# tester-rp.net
KiCad netlist of a schematic drawn in EAGLE
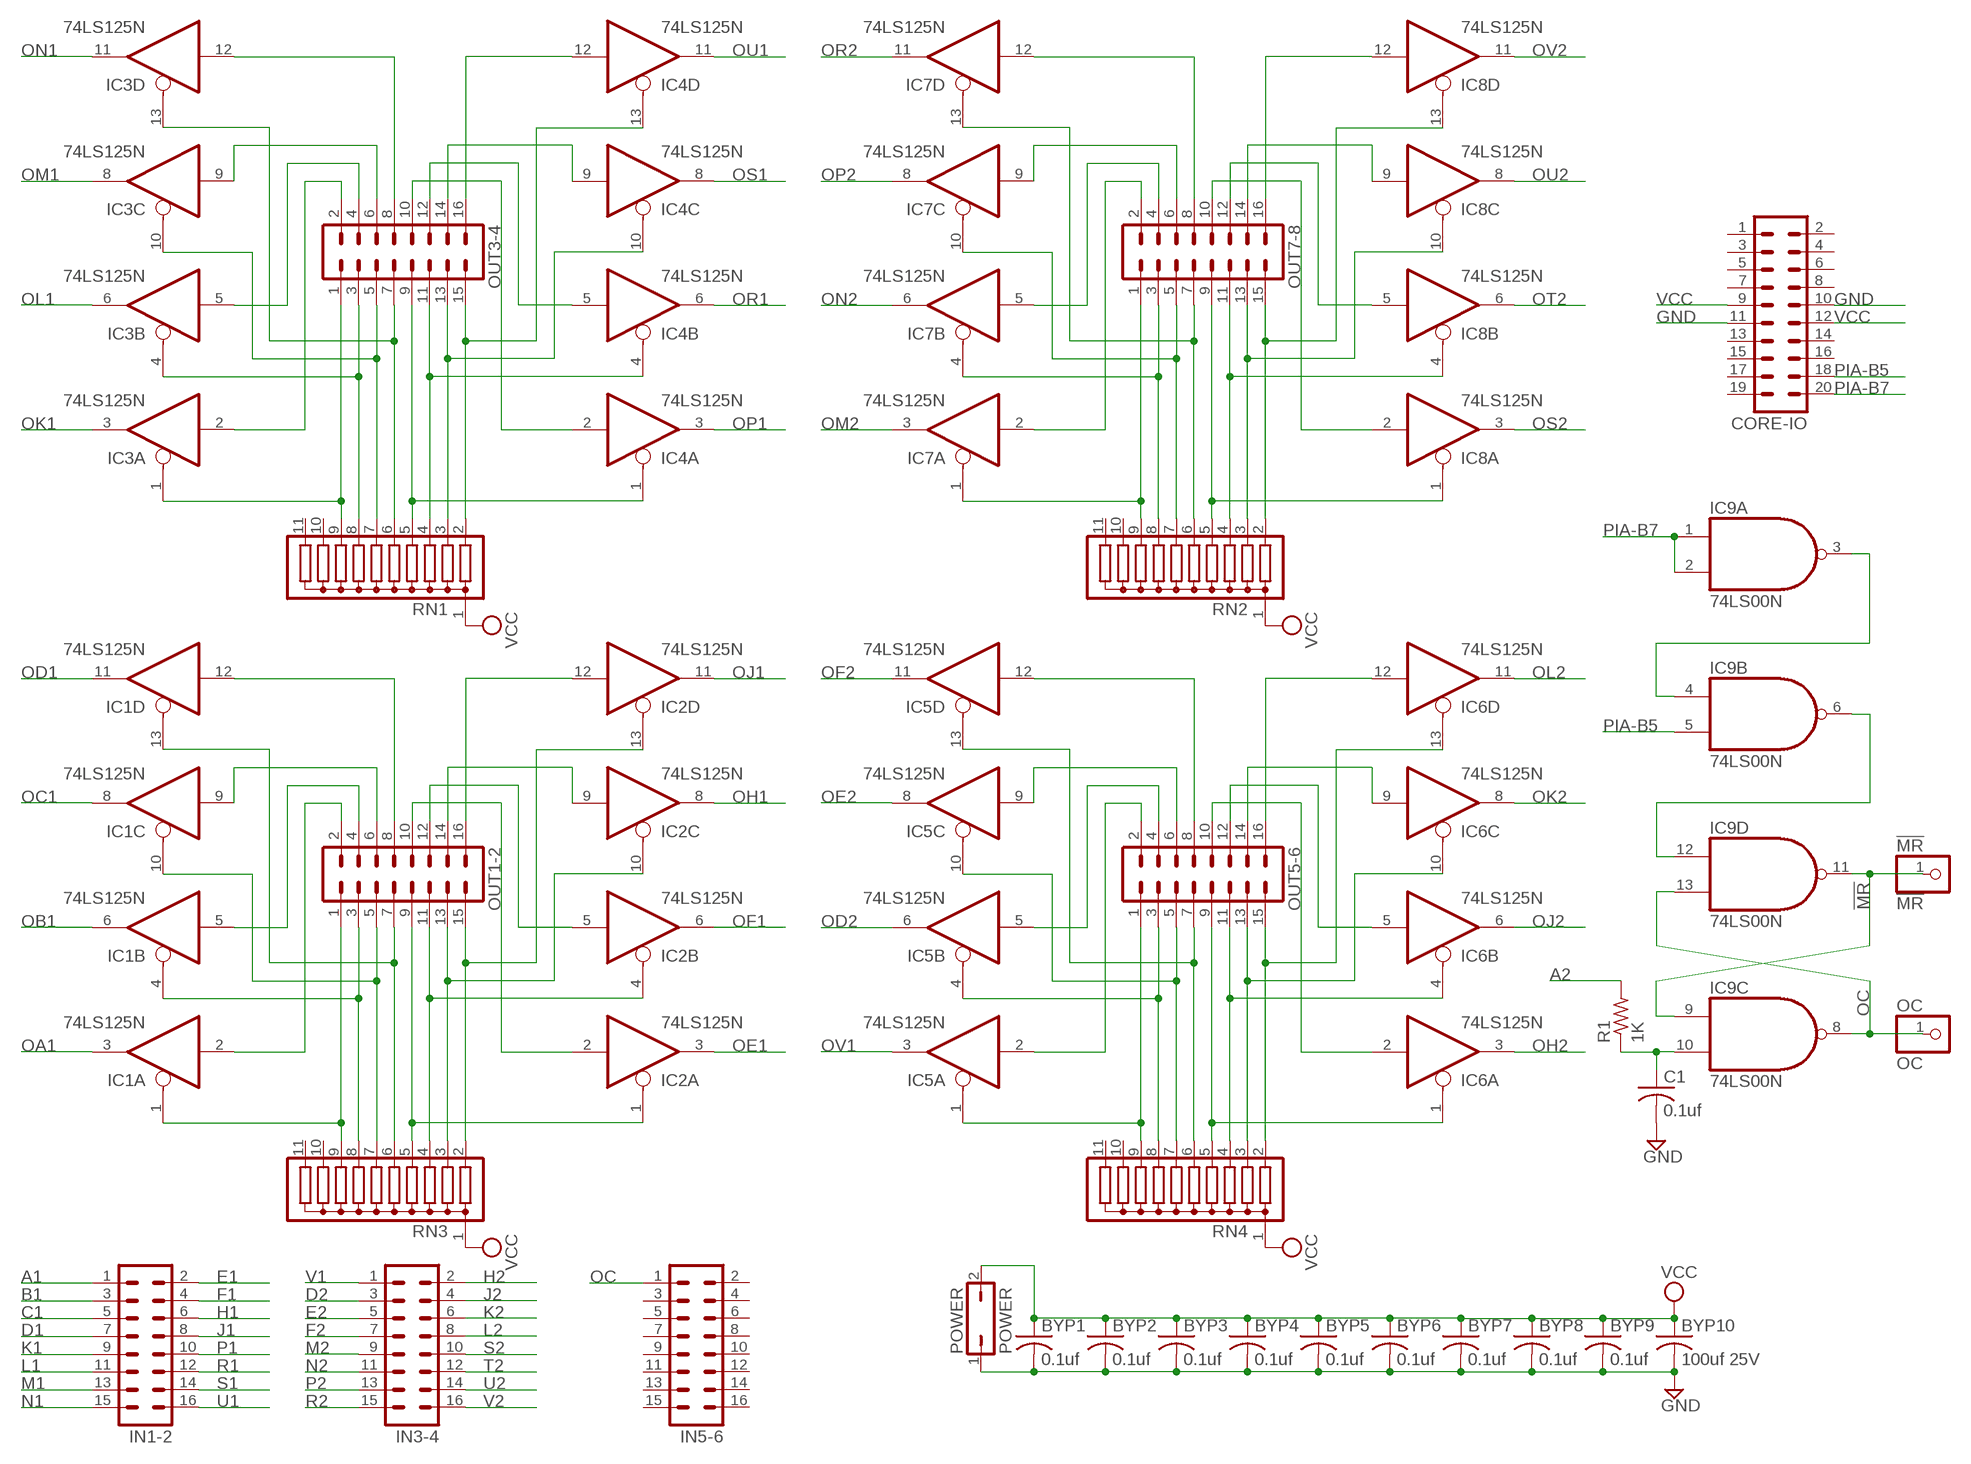
[diagram p0: schematic, sheet 1]
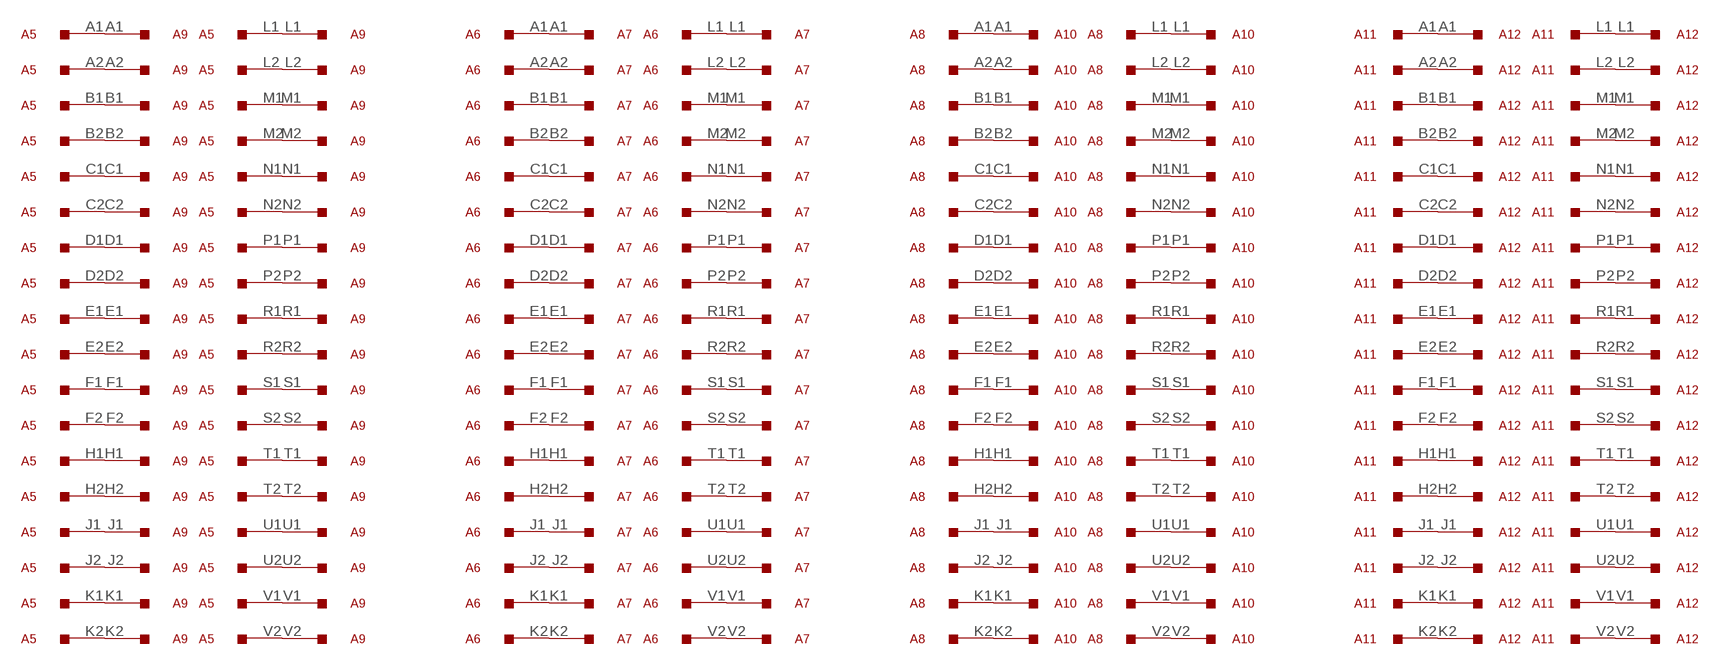
[diagram p1: schematic, sheet 2]
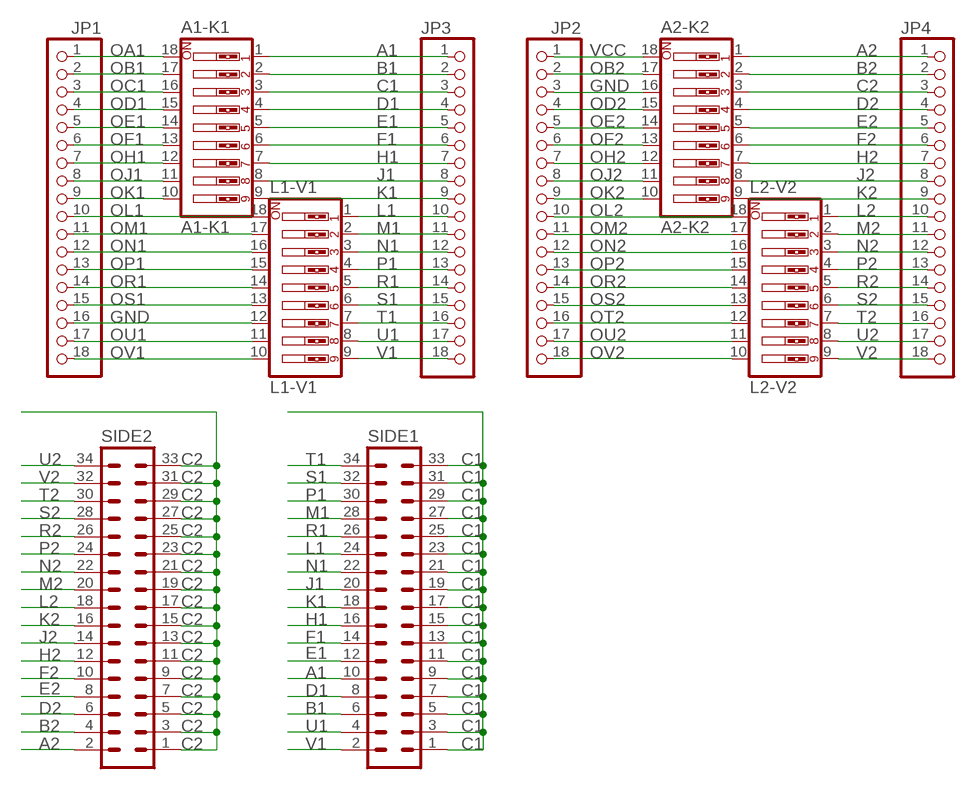
[diagram p2: schematic, sheet 3]

(export (version "E")
  (design (tool "Eeschema 10.0.6"))
  (components
    (comp (ref "!MR")
      (value "!MR")
      (footprint "eagle-import:1X01")
      (libsource (lib "eagle-import") (part "PINHD-1X1"))
    )
    (comp (ref "BYP1")
      (value "0.1uf")
      (footprint "eagle-import:C050-025X075")
      (libsource (lib "eagle-import") (part "C-US050-025X075"))
    )
    (comp (ref "BYP2")
      (value "0.1uf")
      (footprint "eagle-import:C050-025X075")
      (libsource (lib "eagle-import") (part "C-US050-025X075"))
    )
    (comp (ref "BYP3")
      (value "0.1uf")
      (footprint "eagle-import:C050-025X075")
      (libsource (lib "eagle-import") (part "C-US050-025X075"))
    )
    (comp (ref "BYP4")
      (value "0.1uf")
      (footprint "eagle-import:C050-025X075")
      (libsource (lib "eagle-import") (part "C-US050-025X075"))
    )
    (comp (ref "BYP5")
      (value "0.1uf")
      (footprint "eagle-import:C050-025X075")
      (libsource (lib "eagle-import") (part "C-US050-025X075"))
    )
    (comp (ref "BYP6")
      (value "0.1uf")
      (footprint "eagle-import:C050-025X075")
      (libsource (lib "eagle-import") (part "C-US050-025X075"))
    )
    (comp (ref "BYP7")
      (value "0.1uf")
      (footprint "eagle-import:C050-025X075")
      (libsource (lib "eagle-import") (part "C-US050-025X075"))
    )
    (comp (ref "BYP8")
      (value "0.1uf")
      (footprint "eagle-import:C050-025X075")
      (libsource (lib "eagle-import") (part "C-US050-025X075"))
    )
    (comp (ref "BYP9")
      (value "0.1uf")
      (footprint "eagle-import:C050-025X075")
      (libsource (lib "eagle-import") (part "C-US050-025X075"))
    )
    (comp (ref "BYP10")
      (value "100uf 25V")
      (footprint "eagle-import:C150-064X183")
      (libsource (lib "eagle-import") (part "C-US150-064X183"))
    )
    (comp (ref "C1")
      (value "0.1uf")
      (footprint "eagle-import:C050-025X075")
      (libsource (lib "eagle-import") (part "C-US050-025X075"))
    )
    (comp (ref "CORE-IO")
      (value "MA10-2")
      (footprint "eagle-import:MA10-2")
      (libsource (lib "eagle-import") (part "MA10-2"))
    )
    (comp (ref "IC1")
      (value "74LS125N")
      (footprint "eagle-import:DIL14")
      (libsource (lib "eagle-import") (part "74125NLS"))
    )
    (comp (ref "IC2")
      (value "74LS125N")
      (footprint "eagle-import:DIL14")
      (libsource (lib "eagle-import") (part "74125NLS"))
    )
    (comp (ref "IC3")
      (value "74LS125N")
      (footprint "eagle-import:DIL14")
      (libsource (lib "eagle-import") (part "74125NLS"))
    )
    (comp (ref "IC4")
      (value "74LS125N")
      (footprint "eagle-import:DIL14")
      (libsource (lib "eagle-import") (part "74125NLS"))
    )
    (comp (ref "IC5")
      (value "74LS125N")
      (footprint "eagle-import:DIL14")
      (libsource (lib "eagle-import") (part "74125NLS"))
    )
    (comp (ref "IC6")
      (value "74LS125N")
      (footprint "eagle-import:DIL14")
      (libsource (lib "eagle-import") (part "74125NLS"))
    )
    (comp (ref "IC7")
      (value "74LS125N")
      (footprint "eagle-import:DIL14")
      (libsource (lib "eagle-import") (part "74125NLS"))
    )
    (comp (ref "IC8")
      (value "74LS125N")
      (footprint "eagle-import:DIL14")
      (libsource (lib "eagle-import") (part "74125NLS"))
    )
    (comp (ref "IC9")
      (value "74LS00N")
      (footprint "eagle-import:DIL14")
      (libsource (lib "eagle-import") (part "7400NLS"))
    )
    (comp (ref "IN1-2")
      (value "MA08-2")
      (footprint "eagle-import:MA08-2")
      (libsource (lib "eagle-import") (part "MA08-2"))
    )
    (comp (ref "IN3-4")
      (value "MA08-2")
      (footprint "eagle-import:MA08-2")
      (libsource (lib "eagle-import") (part "MA08-2"))
    )
    (comp (ref "IN5-6")
      (value "MA08-2")
      (footprint "eagle-import:MA08-2")
      (libsource (lib "eagle-import") (part "MA08-2"))
    )
    (comp (ref "OC")
      (value "OC")
      (footprint "eagle-import:1X01")
      (libsource (lib "eagle-import") (part "PINHD-1X1"))
    )
    (comp (ref "OUT1-2")
      (value "MA08-2")
      (footprint "eagle-import:MA08-2")
      (libsource (lib "eagle-import") (part "MA08-2"))
    )
    (comp (ref "OUT3-4")
      (value "MA08-2")
      (footprint "eagle-import:MA08-2")
      (libsource (lib "eagle-import") (part "MA08-2"))
    )
    (comp (ref "OUT5-6")
      (value "MA08-2")
      (footprint "eagle-import:MA08-2")
      (libsource (lib "eagle-import") (part "MA08-2"))
    )
    (comp (ref "OUT7-8")
      (value "MA08-2")
      (footprint "eagle-import:MA08-2")
      (libsource (lib "eagle-import") (part "MA08-2"))
    )
    (comp (ref "POWER")
      (value "POWER")
      (footprint "eagle-import:JP1")
      (libsource (lib "eagle-import") (part "JP1Q"))
    )
    (comp (ref "R1")
      (value "1K")
      (footprint "eagle-import:0207_10")
      (libsource (lib "eagle-import") (part "R-US_0207/10"))
    )
    (comp (ref "RN1")
      (value "G10R")
      (footprint "eagle-import:SIL11")
      (libsource (lib "eagle-import") (part "G10R"))
    )
    (comp (ref "RN2")
      (value "G10R")
      (footprint "eagle-import:SIL11")
      (libsource (lib "eagle-import") (part "G10R"))
    )
    (comp (ref "RN3")
      (value "G10R")
      (footprint "eagle-import:SIL11")
      (libsource (lib "eagle-import") (part "G10R"))
    )
    (comp (ref "RN4")
      (value "G10R")
      (footprint "eagle-import:SIL11")
      (libsource (lib "eagle-import") (part "G10R"))
    )
    (comp (ref "A1-K1")
      (value "A1-K1")
      (footprint "eagle-import:EDG-09")
      (libsource (lib "eagle-import") (part "SW_DIP-9"))
    )
    (comp (ref "A2-K2")
      (value "A2-K2")
      (footprint "eagle-import:EDG-09")
      (libsource (lib "eagle-import") (part "SW_DIP-9"))
    )
    (comp (ref "JP1")
      (value "PINHD-1X18")
      (footprint "eagle-import:1X18")
      (libsource (lib "eagle-import") (part "PINHD-1X18"))
    )
    (comp (ref "JP2")
      (value "PINHD-1X18")
      (footprint "eagle-import:1X18")
      (libsource (lib "eagle-import") (part "PINHD-1X18"))
    )
    (comp (ref "JP3")
      (value "PINHD-1X18")
      (footprint "eagle-import:1X18")
      (libsource (lib "eagle-import") (part "PINHD-1X18"))
    )
    (comp (ref "JP4")
      (value "PINHD-1X18")
      (footprint "eagle-import:1X18")
      (libsource (lib "eagle-import") (part "PINHD-1X18"))
    )
    (comp (ref "L1-V1")
      (value "L1-V1")
      (footprint "eagle-import:EDG-09")
      (libsource (lib "eagle-import") (part "SW_DIP-9"))
    )
    (comp (ref "L2-V2")
      (value "L2-V2")
      (footprint "eagle-import:EDG-09")
      (libsource (lib "eagle-import") (part "SW_DIP-9"))
    )
    (comp (ref "SIDE1")
      (value "MA17-2")
      (footprint "eagle-import:MA17-2")
      (libsource (lib "eagle-import") (part "MA17-2"))
    )
    (comp (ref "SIDE2")
      (value "MA17-2")
      (footprint "eagle-import:MA17-2")
      (libsource (lib "eagle-import") (part "MA17-2"))
    )
    (comp (ref "A5")
      (value "M916")
      (footprint "eagle-import:H807")
      (libsource (lib "eagle-import") (part "M916"))
    )
    (comp (ref "A6")
      (value "M916")
      (footprint "eagle-import:H807")
      (libsource (lib "eagle-import") (part "M916"))
    )
    (comp (ref "A7")
      (value "M916")
      (footprint "eagle-import:H807")
      (libsource (lib "eagle-import") (part "M916"))
    )
    (comp (ref "A8")
      (value "M916")
      (footprint "eagle-import:H807")
      (libsource (lib "eagle-import") (part "M916"))
    )
    (comp (ref "A9")
      (value "M916")
      (footprint "eagle-import:H807")
      (libsource (lib "eagle-import") (part "M916"))
    )
    (comp (ref "A10")
      (value "M916")
      (footprint "eagle-import:H807")
      (libsource (lib "eagle-import") (part "M916"))
    )
    (comp (ref "A11")
      (value "M916")
      (footprint "eagle-import:H807")
      (libsource (lib "eagle-import") (part "M916"))
    )
    (comp (ref "A12")
      (value "M916")
      (footprint "eagle-import:H807")
      (libsource (lib "eagle-import") (part "M916"))
    )
  )
  (nets
    (net (code "1") (name "A1") (class "Default")
      (node (ref "A1-K1") (pin "1") (pinfunction "1_1") (pintype "passive"))
      (node (ref "IN1-2") (pin "1") (pinfunction "1_1") (pintype "passive"))
      (node (ref "JP3") (pin "1") (pinfunction "1_1") (pintype "passive"))
      (node (ref "SIDE1") (pin "10") (pinfunction "10_10") (pintype "passive"))
    )
    (net (code "2") (name "A2") (class "Default")
      (node (ref "A2-K2") (pin "1") (pinfunction "1_1") (pintype "passive"))
      (node (ref "JP4") (pin "1") (pinfunction "1_1") (pintype "passive"))
      (node (ref "R1") (pin "2") (pinfunction "2_2") (pintype "passive"))
      (node (ref "SIDE2") (pin "2") (pinfunction "2_2") (pintype "passive"))
    )
    (net (code "3") (name "B1") (class "Default")
      (node (ref "A1-K1") (pin "2") (pinfunction "2_2") (pintype "passive"))
      (node (ref "IN1-2") (pin "3") (pinfunction "3_3") (pintype "passive"))
      (node (ref "JP3") (pin "2") (pinfunction "2_2") (pintype "passive"))
      (node (ref "SIDE1") (pin "6") (pinfunction "6_6") (pintype "passive"))
    )
    (net (code "4") (name "B2") (class "Default")
      (node (ref "A2-K2") (pin "2") (pinfunction "2_2") (pintype "passive"))
      (node (ref "JP4") (pin "2") (pinfunction "2_2") (pintype "passive"))
      (node (ref "SIDE2") (pin "4") (pinfunction "4_4") (pintype "passive"))
    )
    (net (code "5") (name "C1") (class "Default")
      (node (ref "A1-K1") (pin "3") (pinfunction "3_3") (pintype "passive"))
      (node (ref "IN1-2") (pin "5") (pinfunction "5_5") (pintype "passive"))
      (node (ref "JP3") (pin "3") (pinfunction "3_3") (pintype "passive"))
      (node (ref "SIDE1") (pin "1") (pinfunction "1_1") (pintype "passive"))
      (node (ref "SIDE1") (pin "11") (pinfunction "11_11") (pintype "passive"))
      (node (ref "SIDE1") (pin "13") (pinfunction "13_13") (pintype "passive"))
      (node (ref "SIDE1") (pin "15") (pinfunction "15_15") (pintype "passive"))
      (node (ref "SIDE1") (pin "17") (pinfunction "17_17") (pintype "passive"))
      (node (ref "SIDE1") (pin "19") (pinfunction "19_19") (pintype "passive"))
      (node (ref "SIDE1") (pin "21") (pinfunction "21_21") (pintype "passive"))
      (node (ref "SIDE1") (pin "23") (pinfunction "23_23") (pintype "passive"))
      (node (ref "SIDE1") (pin "25") (pinfunction "25_25") (pintype "passive"))
      (node (ref "SIDE1") (pin "27") (pinfunction "27_27") (pintype "passive"))
      (node (ref "SIDE1") (pin "29") (pinfunction "29_29") (pintype "passive"))
      (node (ref "SIDE1") (pin "3") (pinfunction "3_3") (pintype "passive"))
      (node (ref "SIDE1") (pin "31") (pinfunction "31_31") (pintype "passive"))
      (node (ref "SIDE1") (pin "33") (pinfunction "33_33") (pintype "passive"))
      (node (ref "SIDE1") (pin "5") (pinfunction "5_5") (pintype "passive"))
      (node (ref "SIDE1") (pin "7") (pinfunction "7_7") (pintype "passive"))
      (node (ref "SIDE1") (pin "9") (pinfunction "9_9") (pintype "passive"))
    )
    (net (code "6") (name "C2") (class "Default")
      (node (ref "A2-K2") (pin "3") (pinfunction "3_3") (pintype "passive"))
      (node (ref "JP4") (pin "3") (pinfunction "3_3") (pintype "passive"))
      (node (ref "SIDE2") (pin "1") (pinfunction "1_1") (pintype "passive"))
      (node (ref "SIDE2") (pin "11") (pinfunction "11_11") (pintype "passive"))
      (node (ref "SIDE2") (pin "13") (pinfunction "13_13") (pintype "passive"))
      (node (ref "SIDE2") (pin "15") (pinfunction "15_15") (pintype "passive"))
      (node (ref "SIDE2") (pin "17") (pinfunction "17_17") (pintype "passive"))
      (node (ref "SIDE2") (pin "19") (pinfunction "19_19") (pintype "passive"))
      (node (ref "SIDE2") (pin "21") (pinfunction "21_21") (pintype "passive"))
      (node (ref "SIDE2") (pin "23") (pinfunction "23_23") (pintype "passive"))
      (node (ref "SIDE2") (pin "25") (pinfunction "25_25") (pintype "passive"))
      (node (ref "SIDE2") (pin "27") (pinfunction "27_27") (pintype "passive"))
      (node (ref "SIDE2") (pin "29") (pinfunction "29_29") (pintype "passive"))
      (node (ref "SIDE2") (pin "3") (pinfunction "3_3") (pintype "passive"))
      (node (ref "SIDE2") (pin "31") (pinfunction "31_31") (pintype "passive"))
      (node (ref "SIDE2") (pin "33") (pinfunction "33_33") (pintype "passive"))
      (node (ref "SIDE2") (pin "5") (pinfunction "5_5") (pintype "passive"))
      (node (ref "SIDE2") (pin "7") (pinfunction "7_7") (pintype "passive"))
      (node (ref "SIDE2") (pin "9") (pinfunction "9_9") (pintype "passive"))
    )
    (net (code "7") (name "D1") (class "Default")
      (node (ref "A1-K1") (pin "4") (pinfunction "4_4") (pintype "passive"))
      (node (ref "IN1-2") (pin "7") (pinfunction "7_7") (pintype "passive"))
      (node (ref "JP3") (pin "4") (pinfunction "4_4") (pintype "passive"))
      (node (ref "SIDE1") (pin "8") (pinfunction "8_8") (pintype "passive"))
    )
    (net (code "8") (name "D2") (class "Default")
      (node (ref "A2-K2") (pin "4") (pinfunction "4_4") (pintype "passive"))
      (node (ref "IN3-4") (pin "3") (pinfunction "3_3") (pintype "passive"))
      (node (ref "JP4") (pin "4") (pinfunction "4_4") (pintype "passive"))
      (node (ref "SIDE2") (pin "6") (pinfunction "6_6") (pintype "passive"))
    )
    (net (code "9") (name "E1") (class "Default")
      (node (ref "A1-K1") (pin "5") (pinfunction "5_5") (pintype "passive"))
      (node (ref "IN1-2") (pin "2") (pinfunction "2_2") (pintype "passive"))
      (node (ref "JP3") (pin "5") (pinfunction "5_5") (pintype "passive"))
      (node (ref "SIDE1") (pin "12") (pinfunction "12_12") (pintype "passive"))
    )
    (net (code "10") (name "E2") (class "Default")
      (node (ref "A2-K2") (pin "5") (pinfunction "5_5") (pintype "passive"))
      (node (ref "IN3-4") (pin "5") (pinfunction "5_5") (pintype "passive"))
      (node (ref "JP4") (pin "5") (pinfunction "5_5") (pintype "passive"))
      (node (ref "SIDE2") (pin "8") (pinfunction "8_8") (pintype "passive"))
    )
    (net (code "11") (name "F1") (class "Default")
      (node (ref "A1-K1") (pin "6") (pinfunction "6_6") (pintype "passive"))
      (node (ref "IN1-2") (pin "4") (pinfunction "4_4") (pintype "passive"))
      (node (ref "JP3") (pin "6") (pinfunction "6_6") (pintype "passive"))
      (node (ref "SIDE1") (pin "14") (pinfunction "14_14") (pintype "passive"))
    )
    (net (code "12") (name "F2") (class "Default")
      (node (ref "A2-K2") (pin "6") (pinfunction "6_6") (pintype "passive"))
      (node (ref "IN3-4") (pin "7") (pinfunction "7_7") (pintype "passive"))
      (node (ref "JP4") (pin "6") (pinfunction "6_6") (pintype "passive"))
      (node (ref "SIDE2") (pin "10") (pinfunction "10_10") (pintype "passive"))
    )
    (net (code "13") (name "GND") (class "Default")
      (node (ref "A2-K2") (pin "16") (pinfunction "16_16") (pintype "passive"))
      (node (ref "BYP1") (pin "2") (pinfunction "2_2") (pintype "passive"))
      (node (ref "BYP10") (pin "2") (pinfunction "2_2") (pintype "passive"))
      (node (ref "BYP2") (pin "2") (pinfunction "2_2") (pintype "passive"))
      (node (ref "BYP3") (pin "2") (pinfunction "2_2") (pintype "passive"))
      (node (ref "BYP4") (pin "2") (pinfunction "2_2") (pintype "passive"))
      (node (ref "BYP5") (pin "2") (pinfunction "2_2") (pintype "passive"))
      (node (ref "BYP6") (pin "2") (pinfunction "2_2") (pintype "passive"))
      (node (ref "BYP7") (pin "2") (pinfunction "2_2") (pintype "passive"))
      (node (ref "BYP8") (pin "2") (pinfunction "2_2") (pintype "passive"))
      (node (ref "BYP9") (pin "2") (pinfunction "2_2") (pintype "passive"))
      (node (ref "C1") (pin "2") (pinfunction "2_2") (pintype "passive"))
      (node (ref "CORE-IO") (pin "10") (pinfunction "10_10") (pintype "passive"))
      (node (ref "CORE-IO") (pin "11") (pinfunction "11_11") (pintype "passive"))
      (node (ref "JP1") (pin "16") (pinfunction "16_16") (pintype "passive"))
      (node (ref "JP2") (pin "3") (pinfunction "3_3") (pintype "passive"))
      (node (ref "L1-V1") (pin "12") (pinfunction "12_12") (pintype "passive"))
      (node (ref "POWER") (pin "1") (pinfunction "1_1") (pintype "passive"))
    )
    (net (code "14") (name "H1") (class "Default")
      (node (ref "A1-K1") (pin "7") (pinfunction "7_7") (pintype "passive"))
      (node (ref "IN1-2") (pin "6") (pinfunction "6_6") (pintype "passive"))
      (node (ref "JP3") (pin "7") (pinfunction "7_7") (pintype "passive"))
      (node (ref "SIDE1") (pin "16") (pinfunction "16_16") (pintype "passive"))
    )
    (net (code "15") (name "H2") (class "Default")
      (node (ref "A2-K2") (pin "7") (pinfunction "7_7") (pintype "passive"))
      (node (ref "IN3-4") (pin "2") (pinfunction "2_2") (pintype "passive"))
      (node (ref "JP4") (pin "7") (pinfunction "7_7") (pintype "passive"))
      (node (ref "SIDE2") (pin "12") (pinfunction "12_12") (pintype "passive"))
    )
    (net (code "16") (name "J1") (class "Default")
      (node (ref "A1-K1") (pin "8") (pinfunction "8_8") (pintype "passive"))
      (node (ref "IN1-2") (pin "8") (pinfunction "8_8") (pintype "passive"))
      (node (ref "JP3") (pin "8") (pinfunction "8_8") (pintype "passive"))
      (node (ref "SIDE1") (pin "20") (pinfunction "20_20") (pintype "passive"))
    )
    (net (code "17") (name "J2") (class "Default")
      (node (ref "A2-K2") (pin "8") (pinfunction "8_8") (pintype "passive"))
      (node (ref "IN3-4") (pin "4") (pinfunction "4_4") (pintype "passive"))
      (node (ref "JP4") (pin "8") (pinfunction "8_8") (pintype "passive"))
      (node (ref "SIDE2") (pin "14") (pinfunction "14_14") (pintype "passive"))
    )
    (net (code "18") (name "K1") (class "Default")
      (node (ref "A1-K1") (pin "9") (pinfunction "9_9") (pintype "passive"))
      (node (ref "IN1-2") (pin "9") (pinfunction "9_9") (pintype "passive"))
      (node (ref "JP3") (pin "9") (pinfunction "9_9") (pintype "passive"))
      (node (ref "SIDE1") (pin "18") (pinfunction "18_18") (pintype "passive"))
    )
    (net (code "19") (name "K2") (class "Default")
      (node (ref "A2-K2") (pin "9") (pinfunction "9_9") (pintype "passive"))
      (node (ref "IN3-4") (pin "6") (pinfunction "6_6") (pintype "passive"))
      (node (ref "JP4") (pin "9") (pinfunction "9_9") (pintype "passive"))
      (node (ref "SIDE2") (pin "16") (pinfunction "16_16") (pintype "passive"))
    )
    (net (code "20") (name "L1") (class "Default")
      (node (ref "IN1-2") (pin "11") (pinfunction "11_11") (pintype "passive"))
      (node (ref "JP3") (pin "10") (pinfunction "10_10") (pintype "passive"))
      (node (ref "L1-V1") (pin "1") (pinfunction "1_1") (pintype "passive"))
      (node (ref "SIDE1") (pin "24") (pinfunction "24_24") (pintype "passive"))
    )
    (net (code "21") (name "L2") (class "Default")
      (node (ref "IN3-4") (pin "8") (pinfunction "8_8") (pintype "passive"))
      (node (ref "JP4") (pin "10") (pinfunction "10_10") (pintype "passive"))
      (node (ref "L2-V2") (pin "1") (pinfunction "1_1") (pintype "passive"))
      (node (ref "SIDE2") (pin "18") (pinfunction "18_18") (pintype "passive"))
    )
    (net (code "22") (name "M1") (class "Default")
      (node (ref "IN1-2") (pin "13") (pinfunction "13_13") (pintype "passive"))
      (node (ref "JP3") (pin "11") (pinfunction "11_11") (pintype "passive"))
      (node (ref "L1-V1") (pin "2") (pinfunction "2_2") (pintype "passive"))
      (node (ref "SIDE1") (pin "28") (pinfunction "28_28") (pintype "passive"))
    )
    (net (code "23") (name "M2") (class "Default")
      (node (ref "IN3-4") (pin "9") (pinfunction "9_9") (pintype "passive"))
      (node (ref "JP4") (pin "11") (pinfunction "11_11") (pintype "passive"))
      (node (ref "L2-V2") (pin "2") (pinfunction "2_2") (pintype "passive"))
      (node (ref "SIDE2") (pin "20") (pinfunction "20_20") (pintype "passive"))
    )
    (net (code "24") (name "N1") (class "Default")
      (node (ref "IN1-2") (pin "15") (pinfunction "15_15") (pintype "passive"))
      (node (ref "JP3") (pin "12") (pinfunction "12_12") (pintype "passive"))
      (node (ref "L1-V1") (pin "3") (pinfunction "3_3") (pintype "passive"))
      (node (ref "SIDE1") (pin "22") (pinfunction "22_22") (pintype "passive"))
    )
    (net (code "25") (name "N2") (class "Default")
      (node (ref "IN3-4") (pin "11") (pinfunction "11_11") (pintype "passive"))
      (node (ref "JP4") (pin "12") (pinfunction "12_12") (pintype "passive"))
      (node (ref "L2-V2") (pin "3") (pinfunction "3_3") (pintype "passive"))
      (node (ref "SIDE2") (pin "22") (pinfunction "22_22") (pintype "passive"))
    )
    (net (code "26") (name "Net-(A5A-P$2)") (class "Default")
      (node (ref "A5") (pin "A1") (pinfunction "P$2_A1") (pintype "bidirectional"))
      (node (ref "A9") (pin "A1") (pinfunction "P$2_A1") (pintype "bidirectional"))
    )
    (net (code "27") (name "Net-(A5AA-P$2)") (class "Default")
      (node (ref "A5") (pin "R1") (pinfunction "P$2_R1") (pintype "bidirectional"))
      (node (ref "A9") (pin "R1") (pinfunction "P$2_R1") (pintype "bidirectional"))
    )
    (net (code "28") (name "Net-(A5AB-P$2)") (class "Default")
      (node (ref "A5") (pin "R2") (pinfunction "P$2_R2") (pintype "bidirectional"))
      (node (ref "A9") (pin "R2") (pinfunction "P$2_R2") (pintype "bidirectional"))
    )
    (net (code "29") (name "Net-(A5AC-P$2)") (class "Default")
      (node (ref "A5") (pin "S1") (pinfunction "P$2_S1") (pintype "bidirectional"))
      (node (ref "A9") (pin "S1") (pinfunction "P$2_S1") (pintype "bidirectional"))
    )
    (net (code "30") (name "Net-(A5AD-P$2)") (class "Default")
      (node (ref "A5") (pin "S2") (pinfunction "P$2_S2") (pintype "bidirectional"))
      (node (ref "A9") (pin "S2") (pinfunction "P$2_S2") (pintype "bidirectional"))
    )
    (net (code "31") (name "Net-(A5AE-P$2)") (class "Default")
      (node (ref "A5") (pin "T1") (pinfunction "P$2_T1") (pintype "bidirectional"))
      (node (ref "A9") (pin "T1") (pinfunction "P$2_T1") (pintype "bidirectional"))
    )
    (net (code "32") (name "Net-(A5AF-P$2)") (class "Default")
      (node (ref "A5") (pin "T2") (pinfunction "P$2_T2") (pintype "bidirectional"))
      (node (ref "A9") (pin "T2") (pinfunction "P$2_T2") (pintype "bidirectional"))
    )
    (net (code "33") (name "Net-(A5AG-P$2)") (class "Default")
      (node (ref "A5") (pin "U1") (pinfunction "P$2_U1") (pintype "bidirectional"))
      (node (ref "A9") (pin "U1") (pinfunction "P$2_U1") (pintype "bidirectional"))
    )
    (net (code "34") (name "Net-(A5AH-P$2)") (class "Default")
      (node (ref "A5") (pin "U2") (pinfunction "P$2_U2") (pintype "bidirectional"))
      (node (ref "A9") (pin "U2") (pinfunction "P$2_U2") (pintype "bidirectional"))
    )
    (net (code "35") (name "Net-(A5AI-P$2)") (class "Default")
      (node (ref "A5") (pin "V1") (pinfunction "P$2_V1") (pintype "bidirectional"))
      (node (ref "A9") (pin "V1") (pinfunction "P$2_V1") (pintype "bidirectional"))
    )
    (net (code "36") (name "Net-(A5AJ-P$2)") (class "Default")
      (node (ref "A5") (pin "V2") (pinfunction "P$2_V2") (pintype "bidirectional"))
      (node (ref "A9") (pin "V2") (pinfunction "P$2_V2") (pintype "bidirectional"))
    )
    (net (code "37") (name "Net-(A5B-P$2)") (class "Default")
      (node (ref "A5") (pin "A2") (pinfunction "P$2_A2") (pintype "bidirectional"))
      (node (ref "A9") (pin "A2") (pinfunction "P$2_A2") (pintype "bidirectional"))
    )
    (net (code "38") (name "Net-(A5C-P$2)") (class "Default")
      (node (ref "A5") (pin "B1") (pinfunction "P$2_B1") (pintype "bidirectional"))
      (node (ref "A9") (pin "B1") (pinfunction "P$2_B1") (pintype "bidirectional"))
    )
    (net (code "39") (name "Net-(A5D-P$2)") (class "Default")
      (node (ref "A5") (pin "B2") (pinfunction "P$2_B2") (pintype "bidirectional"))
      (node (ref "A9") (pin "B2") (pinfunction "P$2_B2") (pintype "bidirectional"))
    )
    (net (code "40") (name "Net-(A5E-P$2)") (class "Default")
      (node (ref "A5") (pin "C1") (pinfunction "P$2_C1") (pintype "bidirectional"))
      (node (ref "A9") (pin "C1") (pinfunction "P$2_C1") (pintype "bidirectional"))
    )
    (net (code "41") (name "Net-(A5F-P$2)") (class "Default")
      (node (ref "A5") (pin "C2") (pinfunction "P$2_C2") (pintype "bidirectional"))
      (node (ref "A9") (pin "C2") (pinfunction "P$2_C2") (pintype "bidirectional"))
    )
    (net (code "42") (name "Net-(A5G-P$2)") (class "Default")
      (node (ref "A5") (pin "D1") (pinfunction "P$2_D1") (pintype "bidirectional"))
      (node (ref "A9") (pin "D1") (pinfunction "P$2_D1") (pintype "bidirectional"))
    )
    (net (code "43") (name "Net-(A5H-P$2)") (class "Default")
      (node (ref "A5") (pin "D2") (pinfunction "P$2_D2") (pintype "bidirectional"))
      (node (ref "A9") (pin "D2") (pinfunction "P$2_D2") (pintype "bidirectional"))
    )
    (net (code "44") (name "Net-(A5I-P$2)") (class "Default")
      (node (ref "A5") (pin "E1") (pinfunction "P$2_E1") (pintype "bidirectional"))
      (node (ref "A9") (pin "E1") (pinfunction "P$2_E1") (pintype "bidirectional"))
    )
    (net (code "45") (name "Net-(A5J-P$2)") (class "Default")
      (node (ref "A5") (pin "E2") (pinfunction "P$2_E2") (pintype "bidirectional"))
      (node (ref "A9") (pin "E2") (pinfunction "P$2_E2") (pintype "bidirectional"))
    )
    (net (code "46") (name "Net-(A5K-P$2)") (class "Default")
      (node (ref "A5") (pin "F1") (pinfunction "P$2_F1") (pintype "bidirectional"))
      (node (ref "A9") (pin "F1") (pinfunction "P$2_F1") (pintype "bidirectional"))
    )
    (net (code "47") (name "Net-(A5L-P$2)") (class "Default")
      (node (ref "A5") (pin "F2") (pinfunction "P$2_F2") (pintype "bidirectional"))
      (node (ref "A9") (pin "F2") (pinfunction "P$2_F2") (pintype "bidirectional"))
    )
    (net (code "48") (name "Net-(A5M-P$2)") (class "Default")
      (node (ref "A5") (pin "H1") (pinfunction "P$2_H1") (pintype "bidirectional"))
      (node (ref "A9") (pin "H1") (pinfunction "P$2_H1") (pintype "bidirectional"))
    )
    (net (code "49") (name "Net-(A5N-P$2)") (class "Default")
      (node (ref "A5") (pin "H2") (pinfunction "P$2_H2") (pintype "bidirectional"))
      (node (ref "A9") (pin "H2") (pinfunction "P$2_H2") (pintype "bidirectional"))
    )
    (net (code "50") (name "Net-(A5O-P$2)") (class "Default")
      (node (ref "A5") (pin "J1") (pinfunction "P$2_J1") (pintype "bidirectional"))
      (node (ref "A9") (pin "J1") (pinfunction "P$2_J1") (pintype "bidirectional"))
    )
    (net (code "51") (name "Net-(A5P-P$2)") (class "Default")
      (node (ref "A5") (pin "J2") (pinfunction "P$2_J2") (pintype "bidirectional"))
      (node (ref "A9") (pin "J2") (pinfunction "P$2_J2") (pintype "bidirectional"))
    )
    (net (code "52") (name "Net-(A5Q-P$2)") (class "Default")
      (node (ref "A5") (pin "K1") (pinfunction "P$2_K1") (pintype "bidirectional"))
      (node (ref "A9") (pin "K1") (pinfunction "P$2_K1") (pintype "bidirectional"))
    )
    (net (code "53") (name "Net-(A5R-P$2)") (class "Default")
      (node (ref "A5") (pin "K2") (pinfunction "P$2_K2") (pintype "bidirectional"))
      (node (ref "A9") (pin "K2") (pinfunction "P$2_K2") (pintype "bidirectional"))
    )
    (net (code "54") (name "Net-(A5S-P$2)") (class "Default")
      (node (ref "A5") (pin "L1") (pinfunction "P$2_L1") (pintype "bidirectional"))
      (node (ref "A9") (pin "L1") (pinfunction "P$2_L1") (pintype "bidirectional"))
    )
    (net (code "55") (name "Net-(A5T-P$2)") (class "Default")
      (node (ref "A5") (pin "L2") (pinfunction "P$2_L2") (pintype "bidirectional"))
      (node (ref "A9") (pin "L2") (pinfunction "P$2_L2") (pintype "bidirectional"))
    )
    (net (code "56") (name "Net-(A5U-P$2)") (class "Default")
      (node (ref "A5") (pin "M1") (pinfunction "P$2_M1") (pintype "bidirectional"))
      (node (ref "A9") (pin "M1") (pinfunction "P$2_M1") (pintype "bidirectional"))
    )
    (net (code "57") (name "Net-(A5V-P$2)") (class "Default")
      (node (ref "A5") (pin "M2") (pinfunction "P$2_M2") (pintype "bidirectional"))
      (node (ref "A9") (pin "M2") (pinfunction "P$2_M2") (pintype "bidirectional"))
    )
    (net (code "58") (name "Net-(A5W-P$2)") (class "Default")
      (node (ref "A5") (pin "N1") (pinfunction "P$2_N1") (pintype "bidirectional"))
      (node (ref "A9") (pin "N1") (pinfunction "P$2_N1") (pintype "bidirectional"))
    )
    (net (code "59") (name "Net-(A5X-P$2)") (class "Default")
      (node (ref "A5") (pin "N2") (pinfunction "P$2_N2") (pintype "bidirectional"))
      (node (ref "A9") (pin "N2") (pinfunction "P$2_N2") (pintype "bidirectional"))
    )
    (net (code "60") (name "Net-(A5Y-P$2)") (class "Default")
      (node (ref "A5") (pin "P1") (pinfunction "P$2_P1") (pintype "bidirectional"))
      (node (ref "A9") (pin "P1") (pinfunction "P$2_P1") (pintype "bidirectional"))
    )
    (net (code "61") (name "Net-(A5Z-P$2)") (class "Default")
      (node (ref "A5") (pin "P2") (pinfunction "P$2_P2") (pintype "bidirectional"))
      (node (ref "A9") (pin "P2") (pinfunction "P$2_P2") (pintype "bidirectional"))
    )
    (net (code "62") (name "Net-(A6A-P$2)") (class "Default")
      (node (ref "A6") (pin "A1") (pinfunction "P$2_A1") (pintype "bidirectional"))
      (node (ref "A7") (pin "A1") (pinfunction "P$2_A1") (pintype "bidirectional"))
    )
    (net (code "63") (name "Net-(A6AA-P$2)") (class "Default")
      (node (ref "A6") (pin "R1") (pinfunction "P$2_R1") (pintype "bidirectional"))
      (node (ref "A7") (pin "R1") (pinfunction "P$2_R1") (pintype "bidirectional"))
    )
    (net (code "64") (name "Net-(A6AB-P$2)") (class "Default")
      (node (ref "A6") (pin "R2") (pinfunction "P$2_R2") (pintype "bidirectional"))
      (node (ref "A7") (pin "R2") (pinfunction "P$2_R2") (pintype "bidirectional"))
    )
    (net (code "65") (name "Net-(A6AC-P$2)") (class "Default")
      (node (ref "A6") (pin "S1") (pinfunction "P$2_S1") (pintype "bidirectional"))
      (node (ref "A7") (pin "S1") (pinfunction "P$2_S1") (pintype "bidirectional"))
    )
    (net (code "66") (name "Net-(A6AD-P$2)") (class "Default")
      (node (ref "A6") (pin "S2") (pinfunction "P$2_S2") (pintype "bidirectional"))
      (node (ref "A7") (pin "S2") (pinfunction "P$2_S2") (pintype "bidirectional"))
    )
    (net (code "67") (name "Net-(A6AE-P$2)") (class "Default")
      (node (ref "A6") (pin "T1") (pinfunction "P$2_T1") (pintype "bidirectional"))
      (node (ref "A7") (pin "T1") (pinfunction "P$2_T1") (pintype "bidirectional"))
    )
    (net (code "68") (name "Net-(A6AF-P$2)") (class "Default")
      (node (ref "A6") (pin "T2") (pinfunction "P$2_T2") (pintype "bidirectional"))
      (node (ref "A7") (pin "T2") (pinfunction "P$2_T2") (pintype "bidirectional"))
    )
    (net (code "69") (name "Net-(A6AG-P$2)") (class "Default")
      (node (ref "A6") (pin "U1") (pinfunction "P$2_U1") (pintype "bidirectional"))
      (node (ref "A7") (pin "U1") (pinfunction "P$2_U1") (pintype "bidirectional"))
    )
    (net (code "70") (name "Net-(A6AH-P$2)") (class "Default")
      (node (ref "A6") (pin "U2") (pinfunction "P$2_U2") (pintype "bidirectional"))
      (node (ref "A7") (pin "U2") (pinfunction "P$2_U2") (pintype "bidirectional"))
    )
    (net (code "71") (name "Net-(A6AI-P$2)") (class "Default")
      (node (ref "A6") (pin "V1") (pinfunction "P$2_V1") (pintype "bidirectional"))
      (node (ref "A7") (pin "V1") (pinfunction "P$2_V1") (pintype "bidirectional"))
    )
    (net (code "72") (name "Net-(A6AJ-P$2)") (class "Default")
      (node (ref "A6") (pin "V2") (pinfunction "P$2_V2") (pintype "bidirectional"))
      (node (ref "A7") (pin "V2") (pinfunction "P$2_V2") (pintype "bidirectional"))
    )
    (net (code "73") (name "Net-(A6B-P$2)") (class "Default")
      (node (ref "A6") (pin "A2") (pinfunction "P$2_A2") (pintype "bidirectional"))
      (node (ref "A7") (pin "A2") (pinfunction "P$2_A2") (pintype "bidirectional"))
    )
    (net (code "74") (name "Net-(A6C-P$2)") (class "Default")
      (node (ref "A6") (pin "B1") (pinfunction "P$2_B1") (pintype "bidirectional"))
      (node (ref "A7") (pin "B1") (pinfunction "P$2_B1") (pintype "bidirectional"))
    )
    (net (code "75") (name "Net-(A6D-P$2)") (class "Default")
      (node (ref "A6") (pin "B2") (pinfunction "P$2_B2") (pintype "bidirectional"))
      (node (ref "A7") (pin "B2") (pinfunction "P$2_B2") (pintype "bidirectional"))
    )
    (net (code "76") (name "Net-(A6E-P$2)") (class "Default")
      (node (ref "A6") (pin "C1") (pinfunction "P$2_C1") (pintype "bidirectional"))
      (node (ref "A7") (pin "C1") (pinfunction "P$2_C1") (pintype "bidirectional"))
    )
    (net (code "77") (name "Net-(A6F-P$2)") (class "Default")
      (node (ref "A6") (pin "C2") (pinfunction "P$2_C2") (pintype "bidirectional"))
      (node (ref "A7") (pin "C2") (pinfunction "P$2_C2") (pintype "bidirectional"))
    )
    (net (code "78") (name "Net-(A6G-P$2)") (class "Default")
      (node (ref "A6") (pin "D1") (pinfunction "P$2_D1") (pintype "bidirectional"))
      (node (ref "A7") (pin "D1") (pinfunction "P$2_D1") (pintype "bidirectional"))
    )
    (net (code "79") (name "Net-(A6H-P$2)") (class "Default")
      (node (ref "A6") (pin "D2") (pinfunction "P$2_D2") (pintype "bidirectional"))
      (node (ref "A7") (pin "D2") (pinfunction "P$2_D2") (pintype "bidirectional"))
    )
    (net (code "80") (name "Net-(A6I-P$2)") (class "Default")
      (node (ref "A6") (pin "E1") (pinfunction "P$2_E1") (pintype "bidirectional"))
      (node (ref "A7") (pin "E1") (pinfunction "P$2_E1") (pintype "bidirectional"))
    )
    (net (code "81") (name "Net-(A6J-P$2)") (class "Default")
      (node (ref "A6") (pin "E2") (pinfunction "P$2_E2") (pintype "bidirectional"))
      (node (ref "A7") (pin "E2") (pinfunction "P$2_E2") (pintype "bidirectional"))
    )
    (net (code "82") (name "Net-(A6K-P$2)") (class "Default")
      (node (ref "A6") (pin "F1") (pinfunction "P$2_F1") (pintype "bidirectional"))
      (node (ref "A7") (pin "F1") (pinfunction "P$2_F1") (pintype "bidirectional"))
    )
    (net (code "83") (name "Net-(A6L-P$2)") (class "Default")
      (node (ref "A6") (pin "F2") (pinfunction "P$2_F2") (pintype "bidirectional"))
      (node (ref "A7") (pin "F2") (pinfunction "P$2_F2") (pintype "bidirectional"))
    )
    (net (code "84") (name "Net-(A6M-P$2)") (class "Default")
      (node (ref "A6") (pin "H1") (pinfunction "P$2_H1") (pintype "bidirectional"))
      (node (ref "A7") (pin "H1") (pinfunction "P$2_H1") (pintype "bidirectional"))
    )
    (net (code "85") (name "Net-(A6N-P$2)") (class "Default")
      (node (ref "A6") (pin "H2") (pinfunction "P$2_H2") (pintype "bidirectional"))
      (node (ref "A7") (pin "H2") (pinfunction "P$2_H2") (pintype "bidirectional"))
    )
    (net (code "86") (name "Net-(A6O-P$2)") (class "Default")
      (node (ref "A6") (pin "J1") (pinfunction "P$2_J1") (pintype "bidirectional"))
      (node (ref "A7") (pin "J1") (pinfunction "P$2_J1") (pintype "bidirectional"))
    )
    (net (code "87") (name "Net-(A6P-P$2)") (class "Default")
      (node (ref "A6") (pin "J2") (pinfunction "P$2_J2") (pintype "bidirectional"))
      (node (ref "A7") (pin "J2") (pinfunction "P$2_J2") (pintype "bidirectional"))
    )
    (net (code "88") (name "Net-(A6Q-P$2)") (class "Default")
      (node (ref "A6") (pin "K1") (pinfunction "P$2_K1") (pintype "bidirectional"))
      (node (ref "A7") (pin "K1") (pinfunction "P$2_K1") (pintype "bidirectional"))
    )
    (net (code "89") (name "Net-(A6R-P$2)") (class "Default")
      (node (ref "A6") (pin "K2") (pinfunction "P$2_K2") (pintype "bidirectional"))
      (node (ref "A7") (pin "K2") (pinfunction "P$2_K2") (pintype "bidirectional"))
    )
    (net (code "90") (name "Net-(A6S-P$2)") (class "Default")
      (node (ref "A6") (pin "L1") (pinfunction "P$2_L1") (pintype "bidirectional"))
      (node (ref "A7") (pin "L1") (pinfunction "P$2_L1") (pintype "bidirectional"))
    )
    (net (code "91") (name "Net-(A6T-P$2)") (class "Default")
      (node (ref "A6") (pin "L2") (pinfunction "P$2_L2") (pintype "bidirectional"))
      (node (ref "A7") (pin "L2") (pinfunction "P$2_L2") (pintype "bidirectional"))
    )
    (net (code "92") (name "Net-(A6U-P$2)") (class "Default")
      (node (ref "A6") (pin "M1") (pinfunction "P$2_M1") (pintype "bidirectional"))
      (node (ref "A7") (pin "M1") (pinfunction "P$2_M1") (pintype "bidirectional"))
    )
    (net (code "93") (name "Net-(A6V-P$2)") (class "Default")
      (node (ref "A6") (pin "M2") (pinfunction "P$2_M2") (pintype "bidirectional"))
      (node (ref "A7") (pin "M2") (pinfunction "P$2_M2") (pintype "bidirectional"))
    )
    (net (code "94") (name "Net-(A6W-P$2)") (class "Default")
      (node (ref "A6") (pin "N1") (pinfunction "P$2_N1") (pintype "bidirectional"))
      (node (ref "A7") (pin "N1") (pinfunction "P$2_N1") (pintype "bidirectional"))
    )
    (net (code "95") (name "Net-(A6X-P$2)") (class "Default")
      (node (ref "A6") (pin "N2") (pinfunction "P$2_N2") (pintype "bidirectional"))
      (node (ref "A7") (pin "N2") (pinfunction "P$2_N2") (pintype "bidirectional"))
    )
    (net (code "96") (name "Net-(A6Y-P$2)") (class "Default")
      (node (ref "A6") (pin "P1") (pinfunction "P$2_P1") (pintype "bidirectional"))
      (node (ref "A7") (pin "P1") (pinfunction "P$2_P1") (pintype "bidirectional"))
    )
    (net (code "97") (name "Net-(A6Z-P$2)") (class "Default")
      (node (ref "A6") (pin "P2") (pinfunction "P$2_P2") (pintype "bidirectional"))
      (node (ref "A7") (pin "P2") (pinfunction "P$2_P2") (pintype "bidirectional"))
    )
    (net (code "98") (name "Net-(A10A-P$2)") (class "Default")
      (node (ref "A10") (pin "A1") (pinfunction "P$2_A1") (pintype "bidirectional"))
      (node (ref "A8") (pin "A1") (pinfunction "P$2_A1") (pintype "bidirectional"))
    )
    (net (code "99") (name "Net-(A10AA-P$2)") (class "Default")
      (node (ref "A10") (pin "R1") (pinfunction "P$2_R1") (pintype "bidirectional"))
      (node (ref "A8") (pin "R1") (pinfunction "P$2_R1") (pintype "bidirectional"))
    )
    (net (code "100") (name "Net-(A10AB-P$2)") (class "Default")
      (node (ref "A10") (pin "R2") (pinfunction "P$2_R2") (pintype "bidirectional"))
      (node (ref "A8") (pin "R2") (pinfunction "P$2_R2") (pintype "bidirectional"))
    )
    (net (code "101") (name "Net-(A10AC-P$2)") (class "Default")
      (node (ref "A10") (pin "S1") (pinfunction "P$2_S1") (pintype "bidirectional"))
      (node (ref "A8") (pin "S1") (pinfunction "P$2_S1") (pintype "bidirectional"))
    )
    (net (code "102") (name "Net-(A10AD-P$2)") (class "Default")
      (node (ref "A10") (pin "S2") (pinfunction "P$2_S2") (pintype "bidirectional"))
      (node (ref "A8") (pin "S2") (pinfunction "P$2_S2") (pintype "bidirectional"))
    )
    (net (code "103") (name "Net-(A10AE-P$2)") (class "Default")
      (node (ref "A10") (pin "T1") (pinfunction "P$2_T1") (pintype "bidirectional"))
      (node (ref "A8") (pin "T1") (pinfunction "P$2_T1") (pintype "bidirectional"))
    )
    (net (code "104") (name "Net-(A10AF-P$2)") (class "Default")
      (node (ref "A10") (pin "T2") (pinfunction "P$2_T2") (pintype "bidirectional"))
      (node (ref "A8") (pin "T2") (pinfunction "P$2_T2") (pintype "bidirectional"))
    )
    (net (code "105") (name "Net-(A10AG-P$2)") (class "Default")
      (node (ref "A10") (pin "U1") (pinfunction "P$2_U1") (pintype "bidirectional"))
      (node (ref "A8") (pin "U1") (pinfunction "P$2_U1") (pintype "bidirectional"))
    )
    (net (code "106") (name "Net-(A10AH-P$2)") (class "Default")
      (node (ref "A10") (pin "U2") (pinfunction "P$2_U2") (pintype "bidirectional"))
      (node (ref "A8") (pin "U2") (pinfunction "P$2_U2") (pintype "bidirectional"))
    )
    (net (code "107") (name "Net-(A10AI-P$2)") (class "Default")
      (node (ref "A10") (pin "V1") (pinfunction "P$2_V1") (pintype "bidirectional"))
      (node (ref "A8") (pin "V1") (pinfunction "P$2_V1") (pintype "bidirectional"))
    )
    (net (code "108") (name "Net-(A10AJ-P$2)") (class "Default")
      (node (ref "A10") (pin "V2") (pinfunction "P$2_V2") (pintype "bidirectional"))
      (node (ref "A8") (pin "V2") (pinfunction "P$2_V2") (pintype "bidirectional"))
    )
    (net (code "109") (name "Net-(A10B-P$2)") (class "Default")
      (node (ref "A10") (pin "A2") (pinfunction "P$2_A2") (pintype "bidirectional"))
      (node (ref "A8") (pin "A2") (pinfunction "P$2_A2") (pintype "bidirectional"))
    )
    (net (code "110") (name "Net-(A10C-P$2)") (class "Default")
      (node (ref "A10") (pin "B1") (pinfunction "P$2_B1") (pintype "bidirectional"))
      (node (ref "A8") (pin "B1") (pinfunction "P$2_B1") (pintype "bidirectional"))
    )
    (net (code "111") (name "Net-(A10D-P$2)") (class "Default")
      (node (ref "A10") (pin "B2") (pinfunction "P$2_B2") (pintype "bidirectional"))
      (node (ref "A8") (pin "B2") (pinfunction "P$2_B2") (pintype "bidirectional"))
    )
    (net (code "112") (name "Net-(A10E-P$2)") (class "Default")
      (node (ref "A10") (pin "C1") (pinfunction "P$2_C1") (pintype "bidirectional"))
      (node (ref "A8") (pin "C1") (pinfunction "P$2_C1") (pintype "bidirectional"))
    )
    (net (code "113") (name "Net-(A10F-P$2)") (class "Default")
      (node (ref "A10") (pin "C2") (pinfunction "P$2_C2") (pintype "bidirectional"))
      (node (ref "A8") (pin "C2") (pinfunction "P$2_C2") (pintype "bidirectional"))
    )
    (net (code "114") (name "Net-(A10G-P$2)") (class "Default")
      (node (ref "A10") (pin "D1") (pinfunction "P$2_D1") (pintype "bidirectional"))
      (node (ref "A8") (pin "D1") (pinfunction "P$2_D1") (pintype "bidirectional"))
    )
    (net (code "115") (name "Net-(A10H-P$2)") (class "Default")
      (node (ref "A10") (pin "D2") (pinfunction "P$2_D2") (pintype "bidirectional"))
      (node (ref "A8") (pin "D2") (pinfunction "P$2_D2") (pintype "bidirectional"))
    )
    (net (code "116") (name "Net-(A10I-P$2)") (class "Default")
      (node (ref "A10") (pin "E1") (pinfunction "P$2_E1") (pintype "bidirectional"))
      (node (ref "A8") (pin "E1") (pinfunction "P$2_E1") (pintype "bidirectional"))
    )
    (net (code "117") (name "Net-(A10J-P$2)") (class "Default")
      (node (ref "A10") (pin "E2") (pinfunction "P$2_E2") (pintype "bidirectional"))
      (node (ref "A8") (pin "E2") (pinfunction "P$2_E2") (pintype "bidirectional"))
    )
    (net (code "118") (name "Net-(A10K-P$2)") (class "Default")
      (node (ref "A10") (pin "F1") (pinfunction "P$2_F1") (pintype "bidirectional"))
      (node (ref "A8") (pin "F1") (pinfunction "P$2_F1") (pintype "bidirectional"))
    )
    (net (code "119") (name "Net-(A10L-P$2)") (class "Default")
      (node (ref "A10") (pin "F2") (pinfunction "P$2_F2") (pintype "bidirectional"))
      (node (ref "A8") (pin "F2") (pinfunction "P$2_F2") (pintype "bidirectional"))
    )
    (net (code "120") (name "Net-(A10M-P$2)") (class "Default")
      (node (ref "A10") (pin "H1") (pinfunction "P$2_H1") (pintype "bidirectional"))
      (node (ref "A8") (pin "H1") (pinfunction "P$2_H1") (pintype "bidirectional"))
    )
    (net (code "121") (name "Net-(A10N-P$2)") (class "Default")
      (node (ref "A10") (pin "H2") (pinfunction "P$2_H2") (pintype "bidirectional"))
      (node (ref "A8") (pin "H2") (pinfunction "P$2_H2") (pintype "bidirectional"))
    )
    (net (code "122") (name "Net-(A10O-P$2)") (class "Default")
      (node (ref "A10") (pin "J1") (pinfunction "P$2_J1") (pintype "bidirectional"))
      (node (ref "A8") (pin "J1") (pinfunction "P$2_J1") (pintype "bidirectional"))
    )
    (net (code "123") (name "Net-(A10P-P$2)") (class "Default")
      (node (ref "A10") (pin "J2") (pinfunction "P$2_J2") (pintype "bidirectional"))
      (node (ref "A8") (pin "J2") (pinfunction "P$2_J2") (pintype "bidirectional"))
    )
    (net (code "124") (name "Net-(A10Q-P$2)") (class "Default")
      (node (ref "A10") (pin "K1") (pinfunction "P$2_K1") (pintype "bidirectional"))
      (node (ref "A8") (pin "K1") (pinfunction "P$2_K1") (pintype "bidirectional"))
    )
    (net (code "125") (name "Net-(A10R-P$2)") (class "Default")
      (node (ref "A10") (pin "K2") (pinfunction "P$2_K2") (pintype "bidirectional"))
      (node (ref "A8") (pin "K2") (pinfunction "P$2_K2") (pintype "bidirectional"))
    )
    (net (code "126") (name "Net-(A10S-P$2)") (class "Default")
      (node (ref "A10") (pin "L1") (pinfunction "P$2_L1") (pintype "bidirectional"))
      (node (ref "A8") (pin "L1") (pinfunction "P$2_L1") (pintype "bidirectional"))
    )
    (net (code "127") (name "Net-(A10T-P$2)") (class "Default")
      (node (ref "A10") (pin "L2") (pinfunction "P$2_L2") (pintype "bidirectional"))
      (node (ref "A8") (pin "L2") (pinfunction "P$2_L2") (pintype "bidirectional"))
    )
    (net (code "128") (name "Net-(A10U-P$2)") (class "Default")
      (node (ref "A10") (pin "M1") (pinfunction "P$2_M1") (pintype "bidirectional"))
      (node (ref "A8") (pin "M1") (pinfunction "P$2_M1") (pintype "bidirectional"))
    )
    (net (code "129") (name "Net-(A10V-P$2)") (class "Default")
      (node (ref "A10") (pin "M2") (pinfunction "P$2_M2") (pintype "bidirectional"))
      (node (ref "A8") (pin "M2") (pinfunction "P$2_M2") (pintype "bidirectional"))
    )
    (net (code "130") (name "Net-(A10W-P$2)") (class "Default")
      (node (ref "A10") (pin "N1") (pinfunction "P$2_N1") (pintype "bidirectional"))
      (node (ref "A8") (pin "N1") (pinfunction "P$2_N1") (pintype "bidirectional"))
    )
    (net (code "131") (name "Net-(A10X-P$2)") (class "Default")
      (node (ref "A10") (pin "N2") (pinfunction "P$2_N2") (pintype "bidirectional"))
      (node (ref "A8") (pin "N2") (pinfunction "P$2_N2") (pintype "bidirectional"))
    )
    (net (code "132") (name "Net-(A10Y-P$2)") (class "Default")
      (node (ref "A10") (pin "P1") (pinfunction "P$2_P1") (pintype "bidirectional"))
      (node (ref "A8") (pin "P1") (pinfunction "P$2_P1") (pintype "bidirectional"))
    )
    (net (code "133") (name "Net-(A10Z-P$2)") (class "Default")
      (node (ref "A10") (pin "P2") (pinfunction "P$2_P2") (pintype "bidirectional"))
      (node (ref "A8") (pin "P2") (pinfunction "P$2_P2") (pintype "bidirectional"))
    )
    (net (code "134") (name "Net-(A11A-P$2)") (class "Default")
      (node (ref "A11") (pin "A1") (pinfunction "P$2_A1") (pintype "bidirectional"))
      (node (ref "A12") (pin "A1") (pinfunction "P$2_A1") (pintype "bidirectional"))
    )
    (net (code "135") (name "Net-(A11AA-P$2)") (class "Default")
      (node (ref "A11") (pin "R1") (pinfunction "P$2_R1") (pintype "bidirectional"))
      (node (ref "A12") (pin "R1") (pinfunction "P$2_R1") (pintype "bidirectional"))
    )
    (net (code "136") (name "Net-(A11AB-P$2)") (class "Default")
      (node (ref "A11") (pin "R2") (pinfunction "P$2_R2") (pintype "bidirectional"))
      (node (ref "A12") (pin "R2") (pinfunction "P$2_R2") (pintype "bidirectional"))
    )
    (net (code "137") (name "Net-(A11AC-P$2)") (class "Default")
      (node (ref "A11") (pin "S1") (pinfunction "P$2_S1") (pintype "bidirectional"))
      (node (ref "A12") (pin "S1") (pinfunction "P$2_S1") (pintype "bidirectional"))
    )
    (net (code "138") (name "Net-(A11AD-P$2)") (class "Default")
      (node (ref "A11") (pin "S2") (pinfunction "P$2_S2") (pintype "bidirectional"))
      (node (ref "A12") (pin "S2") (pinfunction "P$2_S2") (pintype "bidirectional"))
    )
    (net (code "139") (name "Net-(A11AE-P$2)") (class "Default")
      (node (ref "A11") (pin "T1") (pinfunction "P$2_T1") (pintype "bidirectional"))
      (node (ref "A12") (pin "T1") (pinfunction "P$2_T1") (pintype "bidirectional"))
    )
    (net (code "140") (name "Net-(A11AF-P$2)") (class "Default")
      (node (ref "A11") (pin "T2") (pinfunction "P$2_T2") (pintype "bidirectional"))
      (node (ref "A12") (pin "T2") (pinfunction "P$2_T2") (pintype "bidirectional"))
    )
    (net (code "141") (name "Net-(A11AG-P$2)") (class "Default")
      (node (ref "A11") (pin "U1") (pinfunction "P$2_U1") (pintype "bidirectional"))
      (node (ref "A12") (pin "U1") (pinfunction "P$2_U1") (pintype "bidirectional"))
    )
    (net (code "142") (name "Net-(A11AH-P$2)") (class "Default")
      (node (ref "A11") (pin "U2") (pinfunction "P$2_U2") (pintype "bidirectional"))
      (node (ref "A12") (pin "U2") (pinfunction "P$2_U2") (pintype "bidirectional"))
    )
    (net (code "143") (name "Net-(A11AI-P$2)") (class "Default")
      (node (ref "A11") (pin "V1") (pinfunction "P$2_V1") (pintype "bidirectional"))
      (node (ref "A12") (pin "V1") (pinfunction "P$2_V1") (pintype "bidirectional"))
    )
    (net (code "144") (name "Net-(A11AJ-P$2)") (class "Default")
      (node (ref "A11") (pin "V2") (pinfunction "P$2_V2") (pintype "bidirectional"))
      (node (ref "A12") (pin "V2") (pinfunction "P$2_V2") (pintype "bidirectional"))
    )
    (net (code "145") (name "Net-(A11B-P$2)") (class "Default")
      (node (ref "A11") (pin "A2") (pinfunction "P$2_A2") (pintype "bidirectional"))
      (node (ref "A12") (pin "A2") (pinfunction "P$2_A2") (pintype "bidirectional"))
    )
    (net (code "146") (name "Net-(A11C-P$2)") (class "Default")
      (node (ref "A11") (pin "B1") (pinfunction "P$2_B1") (pintype "bidirectional"))
      (node (ref "A12") (pin "B1") (pinfunction "P$2_B1") (pintype "bidirectional"))
    )
    (net (code "147") (name "Net-(A11D-P$2)") (class "Default")
      (node (ref "A11") (pin "B2") (pinfunction "P$2_B2") (pintype "bidirectional"))
      (node (ref "A12") (pin "B2") (pinfunction "P$2_B2") (pintype "bidirectional"))
    )
    (net (code "148") (name "Net-(A11E-P$2)") (class "Default")
      (node (ref "A11") (pin "C1") (pinfunction "P$2_C1") (pintype "bidirectional"))
      (node (ref "A12") (pin "C1") (pinfunction "P$2_C1") (pintype "bidirectional"))
    )
    (net (code "149") (name "Net-(A11F-P$2)") (class "Default")
      (node (ref "A11") (pin "C2") (pinfunction "P$2_C2") (pintype "bidirectional"))
      (node (ref "A12") (pin "C2") (pinfunction "P$2_C2") (pintype "bidirectional"))
    )
    (net (code "150") (name "Net-(A11G-P$2)") (class "Default")
      (node (ref "A11") (pin "D1") (pinfunction "P$2_D1") (pintype "bidirectional"))
      (node (ref "A12") (pin "D1") (pinfunction "P$2_D1") (pintype "bidirectional"))
    )
    (net (code "151") (name "Net-(A11H-P$2)") (class "Default")
      (node (ref "A11") (pin "D2") (pinfunction "P$2_D2") (pintype "bidirectional"))
      (node (ref "A12") (pin "D2") (pinfunction "P$2_D2") (pintype "bidirectional"))
    )
    (net (code "152") (name "Net-(A11I-P$2)") (class "Default")
      (node (ref "A11") (pin "E1") (pinfunction "P$2_E1") (pintype "bidirectional"))
      (node (ref "A12") (pin "E1") (pinfunction "P$2_E1") (pintype "bidirectional"))
    )
    (net (code "153") (name "Net-(A11J-P$2)") (class "Default")
      (node (ref "A11") (pin "E2") (pinfunction "P$2_E2") (pintype "bidirectional"))
      (node (ref "A12") (pin "E2") (pinfunction "P$2_E2") (pintype "bidirectional"))
    )
    (net (code "154") (name "Net-(A11K-P$2)") (class "Default")
      (node (ref "A11") (pin "F1") (pinfunction "P$2_F1") (pintype "bidirectional"))
      (node (ref "A12") (pin "F1") (pinfunction "P$2_F1") (pintype "bidirectional"))
    )
    (net (code "155") (name "Net-(A11L-P$2)") (class "Default")
      (node (ref "A11") (pin "F2") (pinfunction "P$2_F2") (pintype "bidirectional"))
      (node (ref "A12") (pin "F2") (pinfunction "P$2_F2") (pintype "bidirectional"))
    )
    (net (code "156") (name "Net-(A11M-P$2)") (class "Default")
      (node (ref "A11") (pin "H1") (pinfunction "P$2_H1") (pintype "bidirectional"))
      (node (ref "A12") (pin "H1") (pinfunction "P$2_H1") (pintype "bidirectional"))
    )
    (net (code "157") (name "Net-(A11N-P$2)") (class "Default")
      (node (ref "A11") (pin "H2") (pinfunction "P$2_H2") (pintype "bidirectional"))
      (node (ref "A12") (pin "H2") (pinfunction "P$2_H2") (pintype "bidirectional"))
    )
    (net (code "158") (name "Net-(A11O-P$2)") (class "Default")
      (node (ref "A11") (pin "J1") (pinfunction "P$2_J1") (pintype "bidirectional"))
      (node (ref "A12") (pin "J1") (pinfunction "P$2_J1") (pintype "bidirectional"))
    )
    (net (code "159") (name "Net-(A11P-P$2)") (class "Default")
      (node (ref "A11") (pin "J2") (pinfunction "P$2_J2") (pintype "bidirectional"))
      (node (ref "A12") (pin "J2") (pinfunction "P$2_J2") (pintype "bidirectional"))
    )
    (net (code "160") (name "Net-(A11Q-P$2)") (class "Default")
      (node (ref "A11") (pin "K1") (pinfunction "P$2_K1") (pintype "bidirectional"))
      (node (ref "A12") (pin "K1") (pinfunction "P$2_K1") (pintype "bidirectional"))
    )
    (net (code "161") (name "Net-(A11R-P$2)") (class "Default")
      (node (ref "A11") (pin "K2") (pinfunction "P$2_K2") (pintype "bidirectional"))
      (node (ref "A12") (pin "K2") (pinfunction "P$2_K2") (pintype "bidirectional"))
    )
    (net (code "162") (name "Net-(A11S-P$2)") (class "Default")
      (node (ref "A11") (pin "L1") (pinfunction "P$2_L1") (pintype "bidirectional"))
      (node (ref "A12") (pin "L1") (pinfunction "P$2_L1") (pintype "bidirectional"))
    )
    (net (code "163") (name "Net-(A11T-P$2)") (class "Default")
      (node (ref "A11") (pin "L2") (pinfunction "P$2_L2") (pintype "bidirectional"))
      (node (ref "A12") (pin "L2") (pinfunction "P$2_L2") (pintype "bidirectional"))
    )
    (net (code "164") (name "Net-(A11U-P$2)") (class "Default")
      (node (ref "A11") (pin "M1") (pinfunction "P$2_M1") (pintype "bidirectional"))
      (node (ref "A12") (pin "M1") (pinfunction "P$2_M1") (pintype "bidirectional"))
    )
    (net (code "165") (name "Net-(A11V-P$2)") (class "Default")
      (node (ref "A11") (pin "M2") (pinfunction "P$2_M2") (pintype "bidirectional"))
      (node (ref "A12") (pin "M2") (pinfunction "P$2_M2") (pintype "bidirectional"))
    )
    (net (code "166") (name "Net-(A11W-P$2)") (class "Default")
      (node (ref "A11") (pin "N1") (pinfunction "P$2_N1") (pintype "bidirectional"))
      (node (ref "A12") (pin "N1") (pinfunction "P$2_N1") (pintype "bidirectional"))
    )
    (net (code "167") (name "Net-(A11X-P$2)") (class "Default")
      (node (ref "A11") (pin "N2") (pinfunction "P$2_N2") (pintype "bidirectional"))
      (node (ref "A12") (pin "N2") (pinfunction "P$2_N2") (pintype "bidirectional"))
    )
    (net (code "168") (name "Net-(A11Y-P$2)") (class "Default")
      (node (ref "A11") (pin "P1") (pinfunction "P$2_P1") (pintype "bidirectional"))
      (node (ref "A12") (pin "P1") (pinfunction "P$2_P1") (pintype "bidirectional"))
    )
    (net (code "169") (name "Net-(A11Z-P$2)") (class "Default")
      (node (ref "A11") (pin "P2") (pinfunction "P$2_P2") (pintype "bidirectional"))
      (node (ref "A12") (pin "P2") (pinfunction "P$2_P2") (pintype "bidirectional"))
    )
    (net (code "170") (name "Net-(IC1A-I)") (class "Default")
      (node (ref "IC1") (pin "2") (pinfunction "I_2") (pintype "input"))
      (node (ref "OUT1-2") (pin "2") (pinfunction "2_2") (pintype "passive"))
    )
    (net (code "171") (name "Net-(IC1A-OE)") (class "Default")
      (node (ref "IC1") (pin "1") (pinfunction "OE_1") (pintype "input"))
      (node (ref "OUT1-2") (pin "1") (pinfunction "1_1") (pintype "passive"))
      (node (ref "RN3") (pin "9") (pinfunction "9_9") (pintype "passive"))
    )
    (net (code "172") (name "Net-(IC1B-I)") (class "Default")
      (node (ref "IC1") (pin "5") (pinfunction "I_5") (pintype "input"))
      (node (ref "OUT1-2") (pin "4") (pinfunction "4_4") (pintype "passive"))
    )
    (net (code "173") (name "Net-(IC1B-OE)") (class "Default")
      (node (ref "IC1") (pin "4") (pinfunction "OE_4") (pintype "input"))
      (node (ref "OUT1-2") (pin "3") (pinfunction "3_3") (pintype "passive"))
      (node (ref "RN3") (pin "8") (pinfunction "8_8") (pintype "passive"))
    )
    (net (code "174") (name "Net-(IC1C-I)") (class "Default")
      (node (ref "IC1") (pin "9") (pinfunction "I_9") (pintype "input"))
      (node (ref "OUT1-2") (pin "6") (pinfunction "6_6") (pintype "passive"))
    )
    (net (code "175") (name "Net-(IC1C-OE)") (class "Default")
      (node (ref "IC1") (pin "10") (pinfunction "OE_10") (pintype "input"))
      (node (ref "OUT1-2") (pin "5") (pinfunction "5_5") (pintype "passive"))
      (node (ref "RN3") (pin "7") (pinfunction "7_7") (pintype "passive"))
    )
    (net (code "176") (name "Net-(IC1D-I)") (class "Default")
      (node (ref "IC1") (pin "12") (pinfunction "I_12") (pintype "input"))
      (node (ref "OUT1-2") (pin "8") (pinfunction "8_8") (pintype "passive"))
    )
    (net (code "177") (name "Net-(IC1D-OE)") (class "Default")
      (node (ref "IC1") (pin "13") (pinfunction "OE_13") (pintype "input"))
      (node (ref "OUT1-2") (pin "7") (pinfunction "7_7") (pintype "passive"))
      (node (ref "RN3") (pin "6") (pinfunction "6_6") (pintype "passive"))
    )
    (net (code "178") (name "Net-(IC2A-I)") (class "Default")
      (node (ref "IC2") (pin "2") (pinfunction "I_2") (pintype "input"))
      (node (ref "OUT1-2") (pin "10") (pinfunction "10_10") (pintype "passive"))
    )
    (net (code "179") (name "Net-(IC2A-OE)") (class "Default")
      (node (ref "IC2") (pin "1") (pinfunction "OE_1") (pintype "input"))
      (node (ref "OUT1-2") (pin "9") (pinfunction "9_9") (pintype "passive"))
      (node (ref "RN3") (pin "5") (pinfunction "5_5") (pintype "passive"))
    )
    (net (code "180") (name "Net-(IC2B-I)") (class "Default")
      (node (ref "IC2") (pin "5") (pinfunction "I_5") (pintype "input"))
      (node (ref "OUT1-2") (pin "12") (pinfunction "12_12") (pintype "passive"))
    )
    (net (code "181") (name "Net-(IC2B-OE)") (class "Default")
      (node (ref "IC2") (pin "4") (pinfunction "OE_4") (pintype "input"))
      (node (ref "OUT1-2") (pin "11") (pinfunction "11_11") (pintype "passive"))
      (node (ref "RN3") (pin "4") (pinfunction "4_4") (pintype "passive"))
    )
    (net (code "182") (name "Net-(IC2C-I)") (class "Default")
      (node (ref "IC2") (pin "9") (pinfunction "I_9") (pintype "input"))
      (node (ref "OUT1-2") (pin "14") (pinfunction "14_14") (pintype "passive"))
    )
    (net (code "183") (name "Net-(IC2C-OE)") (class "Default")
      (node (ref "IC2") (pin "10") (pinfunction "OE_10") (pintype "input"))
      (node (ref "OUT1-2") (pin "13") (pinfunction "13_13") (pintype "passive"))
      (node (ref "RN3") (pin "3") (pinfunction "3_3") (pintype "passive"))
    )
    (net (code "184") (name "Net-(IC2D-I)") (class "Default")
      (node (ref "IC2") (pin "12") (pinfunction "I_12") (pintype "input"))
      (node (ref "OUT1-2") (pin "16") (pinfunction "16_16") (pintype "passive"))
    )
    (net (code "185") (name "Net-(IC2D-OE)") (class "Default")
      (node (ref "IC2") (pin "13") (pinfunction "OE_13") (pintype "input"))
      (node (ref "OUT1-2") (pin "15") (pinfunction "15_15") (pintype "passive"))
      (node (ref "RN3") (pin "2") (pinfunction "2_2") (pintype "passive"))
    )
    (net (code "186") (name "Net-(IC3A-I)") (class "Default")
      (node (ref "IC3") (pin "2") (pinfunction "I_2") (pintype "input"))
      (node (ref "OUT3-4") (pin "2") (pinfunction "2_2") (pintype "passive"))
    )
    (net (code "187") (name "Net-(IC3A-OE)") (class "Default")
      (node (ref "IC3") (pin "1") (pinfunction "OE_1") (pintype "input"))
      (node (ref "OUT3-4") (pin "1") (pinfunction "1_1") (pintype "passive"))
      (node (ref "RN1") (pin "9") (pinfunction "9_9") (pintype "passive"))
    )
    (net (code "188") (name "Net-(IC3B-I)") (class "Default")
      (node (ref "IC3") (pin "5") (pinfunction "I_5") (pintype "input"))
      (node (ref "OUT3-4") (pin "4") (pinfunction "4_4") (pintype "passive"))
    )
    (net (code "189") (name "Net-(IC3B-OE)") (class "Default")
      (node (ref "IC3") (pin "4") (pinfunction "OE_4") (pintype "input"))
      (node (ref "OUT3-4") (pin "3") (pinfunction "3_3") (pintype "passive"))
      (node (ref "RN1") (pin "8") (pinfunction "8_8") (pintype "passive"))
    )
    (net (code "190") (name "Net-(IC3C-I)") (class "Default")
      (node (ref "IC3") (pin "9") (pinfunction "I_9") (pintype "input"))
      (node (ref "OUT3-4") (pin "6") (pinfunction "6_6") (pintype "passive"))
    )
    (net (code "191") (name "Net-(IC3C-OE)") (class "Default")
      (node (ref "IC3") (pin "10") (pinfunction "OE_10") (pintype "input"))
      (node (ref "OUT3-4") (pin "5") (pinfunction "5_5") (pintype "passive"))
      (node (ref "RN1") (pin "7") (pinfunction "7_7") (pintype "passive"))
    )
    (net (code "192") (name "Net-(IC3D-I)") (class "Default")
      (node (ref "IC3") (pin "12") (pinfunction "I_12") (pintype "input"))
      (node (ref "OUT3-4") (pin "8") (pinfunction "8_8") (pintype "passive"))
    )
    (net (code "193") (name "Net-(IC3D-OE)") (class "Default")
      (node (ref "IC3") (pin "13") (pinfunction "OE_13") (pintype "input"))
      (node (ref "OUT3-4") (pin "7") (pinfunction "7_7") (pintype "passive"))
      (node (ref "RN1") (pin "6") (pinfunction "6_6") (pintype "passive"))
    )
    (net (code "194") (name "Net-(IC4A-I)") (class "Default")
      (node (ref "IC4") (pin "2") (pinfunction "I_2") (pintype "input"))
      (node (ref "OUT3-4") (pin "10") (pinfunction "10_10") (pintype "passive"))
    )
    (net (code "195") (name "Net-(IC4A-OE)") (class "Default")
      (node (ref "IC4") (pin "1") (pinfunction "OE_1") (pintype "input"))
      (node (ref "OUT3-4") (pin "9") (pinfunction "9_9") (pintype "passive"))
      (node (ref "RN1") (pin "5") (pinfunction "5_5") (pintype "passive"))
    )
    (net (code "196") (name "Net-(IC4B-I)") (class "Default")
      (node (ref "IC4") (pin "5") (pinfunction "I_5") (pintype "input"))
      (node (ref "OUT3-4") (pin "12") (pinfunction "12_12") (pintype "passive"))
    )
    (net (code "197") (name "Net-(IC4B-OE)") (class "Default")
      (node (ref "IC4") (pin "4") (pinfunction "OE_4") (pintype "input"))
      (node (ref "OUT3-4") (pin "11") (pinfunction "11_11") (pintype "passive"))
      (node (ref "RN1") (pin "4") (pinfunction "4_4") (pintype "passive"))
    )
    (net (code "198") (name "Net-(IC4C-I)") (class "Default")
      (node (ref "IC4") (pin "9") (pinfunction "I_9") (pintype "input"))
      (node (ref "OUT3-4") (pin "14") (pinfunction "14_14") (pintype "passive"))
    )
    (net (code "199") (name "Net-(IC4C-OE)") (class "Default")
      (node (ref "IC4") (pin "10") (pinfunction "OE_10") (pintype "input"))
      (node (ref "OUT3-4") (pin "13") (pinfunction "13_13") (pintype "passive"))
      (node (ref "RN1") (pin "3") (pinfunction "3_3") (pintype "passive"))
    )
    (net (code "200") (name "Net-(IC4D-I)") (class "Default")
      (node (ref "IC4") (pin "12") (pinfunction "I_12") (pintype "input"))
      (node (ref "OUT3-4") (pin "16") (pinfunction "16_16") (pintype "passive"))
    )
    (net (code "201") (name "Net-(IC4D-OE)") (class "Default")
      (node (ref "IC4") (pin "13") (pinfunction "OE_13") (pintype "input"))
      (node (ref "OUT3-4") (pin "15") (pinfunction "15_15") (pintype "passive"))
      (node (ref "RN1") (pin "2") (pinfunction "2_2") (pintype "passive"))
    )
    (net (code "202") (name "Net-(IC5A-I)") (class "Default")
      (node (ref "IC5") (pin "2") (pinfunction "I_2") (pintype "input"))
      (node (ref "OUT5-6") (pin "2") (pinfunction "2_2") (pintype "passive"))
    )
    (net (code "203") (name "Net-(IC5A-OE)") (class "Default")
      (node (ref "IC5") (pin "1") (pinfunction "OE_1") (pintype "input"))
      (node (ref "OUT5-6") (pin "1") (pinfunction "1_1") (pintype "passive"))
      (node (ref "RN4") (pin "9") (pinfunction "9_9") (pintype "passive"))
    )
    (net (code "204") (name "Net-(IC5B-I)") (class "Default")
      (node (ref "IC5") (pin "5") (pinfunction "I_5") (pintype "input"))
      (node (ref "OUT5-6") (pin "4") (pinfunction "4_4") (pintype "passive"))
    )
    (net (code "205") (name "Net-(IC5B-OE)") (class "Default")
      (node (ref "IC5") (pin "4") (pinfunction "OE_4") (pintype "input"))
      (node (ref "OUT5-6") (pin "3") (pinfunction "3_3") (pintype "passive"))
      (node (ref "RN4") (pin "8") (pinfunction "8_8") (pintype "passive"))
    )
    (net (code "206") (name "Net-(IC5C-I)") (class "Default")
      (node (ref "IC5") (pin "9") (pinfunction "I_9") (pintype "input"))
      (node (ref "OUT5-6") (pin "6") (pinfunction "6_6") (pintype "passive"))
    )
    (net (code "207") (name "Net-(IC5C-OE)") (class "Default")
      (node (ref "IC5") (pin "10") (pinfunction "OE_10") (pintype "input"))
      (node (ref "OUT5-6") (pin "5") (pinfunction "5_5") (pintype "passive"))
      (node (ref "RN4") (pin "7") (pinfunction "7_7") (pintype "passive"))
    )
    (net (code "208") (name "Net-(IC5D-I)") (class "Default")
      (node (ref "IC5") (pin "12") (pinfunction "I_12") (pintype "input"))
      (node (ref "OUT5-6") (pin "8") (pinfunction "8_8") (pintype "passive"))
    )
    (net (code "209") (name "Net-(IC5D-OE)") (class "Default")
      (node (ref "IC5") (pin "13") (pinfunction "OE_13") (pintype "input"))
      (node (ref "OUT5-6") (pin "7") (pinfunction "7_7") (pintype "passive"))
      (node (ref "RN4") (pin "6") (pinfunction "6_6") (pintype "passive"))
    )
    (net (code "210") (name "Net-(IC6A-I)") (class "Default")
      (node (ref "IC6") (pin "2") (pinfunction "I_2") (pintype "input"))
      (node (ref "OUT5-6") (pin "10") (pinfunction "10_10") (pintype "passive"))
    )
    (net (code "211") (name "Net-(IC6A-OE)") (class "Default")
      (node (ref "IC6") (pin "1") (pinfunction "OE_1") (pintype "input"))
      (node (ref "OUT5-6") (pin "9") (pinfunction "9_9") (pintype "passive"))
      (node (ref "RN4") (pin "5") (pinfunction "5_5") (pintype "passive"))
    )
    (net (code "212") (name "Net-(IC6B-I)") (class "Default")
      (node (ref "IC6") (pin "5") (pinfunction "I_5") (pintype "input"))
      (node (ref "OUT5-6") (pin "12") (pinfunction "12_12") (pintype "passive"))
    )
    (net (code "213") (name "Net-(IC6B-OE)") (class "Default")
      (node (ref "IC6") (pin "4") (pinfunction "OE_4") (pintype "input"))
      (node (ref "OUT5-6") (pin "11") (pinfunction "11_11") (pintype "passive"))
      (node (ref "RN4") (pin "4") (pinfunction "4_4") (pintype "passive"))
    )
    (net (code "214") (name "Net-(IC6C-I)") (class "Default")
      (node (ref "IC6") (pin "9") (pinfunction "I_9") (pintype "input"))
      (node (ref "OUT5-6") (pin "14") (pinfunction "14_14") (pintype "passive"))
    )
    (net (code "215") (name "Net-(IC6C-OE)") (class "Default")
      (node (ref "IC6") (pin "10") (pinfunction "OE_10") (pintype "input"))
      (node (ref "OUT5-6") (pin "13") (pinfunction "13_13") (pintype "passive"))
      (node (ref "RN4") (pin "3") (pinfunction "3_3") (pintype "passive"))
    )
    (net (code "216") (name "Net-(IC6D-I)") (class "Default")
      (node (ref "IC6") (pin "12") (pinfunction "I_12") (pintype "input"))
      (node (ref "OUT5-6") (pin "16") (pinfunction "16_16") (pintype "passive"))
    )
    (net (code "217") (name "Net-(IC6D-OE)") (class "Default")
      (node (ref "IC6") (pin "13") (pinfunction "OE_13") (pintype "input"))
      (node (ref "OUT5-6") (pin "15") (pinfunction "15_15") (pintype "passive"))
      (node (ref "RN4") (pin "2") (pinfunction "2_2") (pintype "passive"))
    )
    (net (code "218") (name "Net-(IC7A-I)") (class "Default")
      (node (ref "IC7") (pin "2") (pinfunction "I_2") (pintype "input"))
      (node (ref "OUT7-8") (pin "2") (pinfunction "2_2") (pintype "passive"))
    )
    (net (code "219") (name "Net-(IC7A-OE)") (class "Default")
      (node (ref "IC7") (pin "1") (pinfunction "OE_1") (pintype "input"))
      (node (ref "OUT7-8") (pin "1") (pinfunction "1_1") (pintype "passive"))
      (node (ref "RN2") (pin "9") (pinfunction "9_9") (pintype "passive"))
    )
    (net (code "220") (name "Net-(IC7B-I)") (class "Default")
      (node (ref "IC7") (pin "5") (pinfunction "I_5") (pintype "input"))
      (node (ref "OUT7-8") (pin "4") (pinfunction "4_4") (pintype "passive"))
    )
    (net (code "221") (name "Net-(IC7B-OE)") (class "Default")
      (node (ref "IC7") (pin "4") (pinfunction "OE_4") (pintype "input"))
      (node (ref "OUT7-8") (pin "3") (pinfunction "3_3") (pintype "passive"))
      (node (ref "RN2") (pin "8") (pinfunction "8_8") (pintype "passive"))
    )
    (net (code "222") (name "Net-(IC7C-I)") (class "Default")
      (node (ref "IC7") (pin "9") (pinfunction "I_9") (pintype "input"))
      (node (ref "OUT7-8") (pin "6") (pinfunction "6_6") (pintype "passive"))
    )
    (net (code "223") (name "Net-(IC7C-OE)") (class "Default")
      (node (ref "IC7") (pin "10") (pinfunction "OE_10") (pintype "input"))
      (node (ref "OUT7-8") (pin "5") (pinfunction "5_5") (pintype "passive"))
      (node (ref "RN2") (pin "7") (pinfunction "7_7") (pintype "passive"))
    )
    (net (code "224") (name "Net-(IC7D-I)") (class "Default")
      (node (ref "IC7") (pin "12") (pinfunction "I_12") (pintype "input"))
      (node (ref "OUT7-8") (pin "8") (pinfunction "8_8") (pintype "passive"))
    )
    (net (code "225") (name "Net-(IC7D-OE)") (class "Default")
      (node (ref "IC7") (pin "13") (pinfunction "OE_13") (pintype "input"))
      (node (ref "OUT7-8") (pin "7") (pinfunction "7_7") (pintype "passive"))
      (node (ref "RN2") (pin "6") (pinfunction "6_6") (pintype "passive"))
    )
    (net (code "226") (name "Net-(IC8A-I)") (class "Default")
      (node (ref "IC8") (pin "2") (pinfunction "I_2") (pintype "input"))
      (node (ref "OUT7-8") (pin "10") (pinfunction "10_10") (pintype "passive"))
    )
    (net (code "227") (name "Net-(IC8A-OE)") (class "Default")
      (node (ref "IC8") (pin "1") (pinfunction "OE_1") (pintype "input"))
      (node (ref "OUT7-8") (pin "9") (pinfunction "9_9") (pintype "passive"))
      (node (ref "RN2") (pin "5") (pinfunction "5_5") (pintype "passive"))
    )
    (net (code "228") (name "Net-(IC8B-I)") (class "Default")
      (node (ref "IC8") (pin "5") (pinfunction "I_5") (pintype "input"))
      (node (ref "OUT7-8") (pin "12") (pinfunction "12_12") (pintype "passive"))
    )
    (net (code "229") (name "Net-(IC8B-OE)") (class "Default")
      (node (ref "IC8") (pin "4") (pinfunction "OE_4") (pintype "input"))
      (node (ref "OUT7-8") (pin "11") (pinfunction "11_11") (pintype "passive"))
      (node (ref "RN2") (pin "4") (pinfunction "4_4") (pintype "passive"))
    )
    (net (code "230") (name "Net-(IC8C-I)") (class "Default")
      (node (ref "IC8") (pin "9") (pinfunction "I_9") (pintype "input"))
      (node (ref "OUT7-8") (pin "14") (pinfunction "14_14") (pintype "passive"))
    )
    (net (code "231") (name "Net-(IC8C-OE)") (class "Default")
      (node (ref "IC8") (pin "10") (pinfunction "OE_10") (pintype "input"))
      (node (ref "OUT7-8") (pin "13") (pinfunction "13_13") (pintype "passive"))
      (node (ref "RN2") (pin "3") (pinfunction "3_3") (pintype "passive"))
    )
    (net (code "232") (name "Net-(IC8D-I)") (class "Default")
      (node (ref "IC8") (pin "12") (pinfunction "I_12") (pintype "input"))
      (node (ref "OUT7-8") (pin "16") (pinfunction "16_16") (pintype "passive"))
    )
    (net (code "233") (name "Net-(IC8D-OE)") (class "Default")
      (node (ref "IC8") (pin "13") (pinfunction "OE_13") (pintype "input"))
      (node (ref "OUT7-8") (pin "15") (pinfunction "15_15") (pintype "passive"))
      (node (ref "RN2") (pin "2") (pinfunction "2_2") (pintype "passive"))
    )
    (net (code "234") (name "Net-(IC9A-O)") (class "Default")
      (node (ref "IC9") (pin "3") (pinfunction "O_3") (pintype "output"))
      (node (ref "IC9") (pin "4") (pinfunction "I0_4") (pintype "input"))
    )
    (net (code "235") (name "Net-(IC9B-O)") (class "Default")
      (node (ref "IC9") (pin "12") (pinfunction "I0_12") (pintype "input"))
      (node (ref "IC9") (pin "6") (pinfunction "O_6") (pintype "output"))
    )
    (net (code "236") (name "Net-(IC9C-I1)") (class "Default")
      (node (ref "C1") (pin "1") (pinfunction "1_1") (pintype "passive"))
      (node (ref "IC9") (pin "10") (pinfunction "I1_10") (pintype "input"))
      (node (ref "R1") (pin "1") (pinfunction "1_1") (pintype "passive"))
    )
    (net (code "237") (name "OA1") (class "Default")
      (node (ref "A1-K1") (pin "18") (pinfunction "18_18") (pintype "passive"))
      (node (ref "IC1") (pin "3") (pinfunction "O_3") (pintype "tri_state"))
      (node (ref "JP1") (pin "1") (pinfunction "1_1") (pintype "passive"))
    )
    (net (code "238") (name "OB1") (class "Default")
      (node (ref "A1-K1") (pin "17") (pinfunction "17_17") (pintype "passive"))
      (node (ref "IC1") (pin "6") (pinfunction "O_6") (pintype "tri_state"))
      (node (ref "JP1") (pin "2") (pinfunction "2_2") (pintype "passive"))
    )
    (net (code "239") (name "OB2") (class "Default")
      (node (ref "A2-K2") (pin "17") (pinfunction "17_17") (pintype "passive"))
      (node (ref "JP2") (pin "2") (pinfunction "2_2") (pintype "passive"))
    )
    (net (code "240") (name "OC") (class "Default")
      (node (ref "IC9") (pin "13") (pinfunction "I1_13") (pintype "input"))
      (node (ref "IC9") (pin "8") (pinfunction "O_8") (pintype "output"))
      (node (ref "IN5-6") (pin "1") (pinfunction "1_1") (pintype "passive"))
      (node (ref "OC") (pin "1") (pinfunction "1_1") (pintype "passive"))
    )
    (net (code "241") (name "OC1") (class "Default")
      (node (ref "A1-K1") (pin "16") (pinfunction "16_16") (pintype "passive"))
      (node (ref "IC1") (pin "8") (pinfunction "O_8") (pintype "tri_state"))
      (node (ref "JP1") (pin "3") (pinfunction "3_3") (pintype "passive"))
    )
    (net (code "242") (name "OD1") (class "Default")
      (node (ref "A1-K1") (pin "15") (pinfunction "15_15") (pintype "passive"))
      (node (ref "IC1") (pin "11") (pinfunction "O_11") (pintype "tri_state"))
      (node (ref "JP1") (pin "4") (pinfunction "4_4") (pintype "passive"))
    )
    (net (code "243") (name "OD2") (class "Default")
      (node (ref "A2-K2") (pin "15") (pinfunction "15_15") (pintype "passive"))
      (node (ref "IC5") (pin "6") (pinfunction "O_6") (pintype "tri_state"))
      (node (ref "JP2") (pin "4") (pinfunction "4_4") (pintype "passive"))
    )
    (net (code "244") (name "OE1") (class "Default")
      (node (ref "A1-K1") (pin "14") (pinfunction "14_14") (pintype "passive"))
      (node (ref "IC2") (pin "3") (pinfunction "O_3") (pintype "tri_state"))
      (node (ref "JP1") (pin "5") (pinfunction "5_5") (pintype "passive"))
    )
    (net (code "245") (name "OE2") (class "Default")
      (node (ref "A2-K2") (pin "14") (pinfunction "14_14") (pintype "passive"))
      (node (ref "IC5") (pin "8") (pinfunction "O_8") (pintype "tri_state"))
      (node (ref "JP2") (pin "5") (pinfunction "5_5") (pintype "passive"))
    )
    (net (code "246") (name "OF1") (class "Default")
      (node (ref "A1-K1") (pin "13") (pinfunction "13_13") (pintype "passive"))
      (node (ref "IC2") (pin "6") (pinfunction "O_6") (pintype "tri_state"))
      (node (ref "JP1") (pin "6") (pinfunction "6_6") (pintype "passive"))
    )
    (net (code "247") (name "OF2") (class "Default")
      (node (ref "A2-K2") (pin "13") (pinfunction "13_13") (pintype "passive"))
      (node (ref "IC5") (pin "11") (pinfunction "O_11") (pintype "tri_state"))
      (node (ref "JP2") (pin "6") (pinfunction "6_6") (pintype "passive"))
    )
    (net (code "248") (name "OH1") (class "Default")
      (node (ref "A1-K1") (pin "12") (pinfunction "12_12") (pintype "passive"))
      (node (ref "IC2") (pin "8") (pinfunction "O_8") (pintype "tri_state"))
      (node (ref "JP1") (pin "7") (pinfunction "7_7") (pintype "passive"))
    )
    (net (code "249") (name "OH2") (class "Default")
      (node (ref "A2-K2") (pin "12") (pinfunction "12_12") (pintype "passive"))
      (node (ref "IC6") (pin "3") (pinfunction "O_3") (pintype "tri_state"))
      (node (ref "JP2") (pin "7") (pinfunction "7_7") (pintype "passive"))
    )
    (net (code "250") (name "OJ1") (class "Default")
      (node (ref "A1-K1") (pin "11") (pinfunction "11_11") (pintype "passive"))
      (node (ref "IC2") (pin "11") (pinfunction "O_11") (pintype "tri_state"))
      (node (ref "JP1") (pin "8") (pinfunction "8_8") (pintype "passive"))
    )
    (net (code "251") (name "OJ2") (class "Default")
      (node (ref "A2-K2") (pin "11") (pinfunction "11_11") (pintype "passive"))
      (node (ref "IC6") (pin "6") (pinfunction "O_6") (pintype "tri_state"))
      (node (ref "JP2") (pin "8") (pinfunction "8_8") (pintype "passive"))
    )
    (net (code "252") (name "OK1") (class "Default")
      (node (ref "A1-K1") (pin "10") (pinfunction "10_10") (pintype "passive"))
      (node (ref "IC3") (pin "3") (pinfunction "O_3") (pintype "tri_state"))
      (node (ref "JP1") (pin "9") (pinfunction "9_9") (pintype "passive"))
    )
    (net (code "253") (name "OK2") (class "Default")
      (node (ref "A2-K2") (pin "10") (pinfunction "10_10") (pintype "passive"))
      (node (ref "IC6") (pin "8") (pinfunction "O_8") (pintype "tri_state"))
      (node (ref "JP2") (pin "9") (pinfunction "9_9") (pintype "passive"))
    )
    (net (code "254") (name "OL1") (class "Default")
      (node (ref "IC3") (pin "6") (pinfunction "O_6") (pintype "tri_state"))
      (node (ref "JP1") (pin "10") (pinfunction "10_10") (pintype "passive"))
      (node (ref "L1-V1") (pin "18") (pinfunction "18_18") (pintype "passive"))
    )
    (net (code "255") (name "OL2") (class "Default")
      (node (ref "IC6") (pin "11") (pinfunction "O_11") (pintype "tri_state"))
      (node (ref "JP2") (pin "10") (pinfunction "10_10") (pintype "passive"))
      (node (ref "L2-V2") (pin "18") (pinfunction "18_18") (pintype "passive"))
    )
    (net (code "256") (name "OM1") (class "Default")
      (node (ref "IC3") (pin "8") (pinfunction "O_8") (pintype "tri_state"))
      (node (ref "JP1") (pin "11") (pinfunction "11_11") (pintype "passive"))
      (node (ref "L1-V1") (pin "17") (pinfunction "17_17") (pintype "passive"))
    )
    (net (code "257") (name "OM2") (class "Default")
      (node (ref "IC7") (pin "3") (pinfunction "O_3") (pintype "tri_state"))
      (node (ref "JP2") (pin "11") (pinfunction "11_11") (pintype "passive"))
      (node (ref "L2-V2") (pin "17") (pinfunction "17_17") (pintype "passive"))
    )
    (net (code "258") (name "ON1") (class "Default")
      (node (ref "IC3") (pin "11") (pinfunction "O_11") (pintype "tri_state"))
      (node (ref "JP1") (pin "12") (pinfunction "12_12") (pintype "passive"))
      (node (ref "L1-V1") (pin "16") (pinfunction "16_16") (pintype "passive"))
    )
    (net (code "259") (name "ON2") (class "Default")
      (node (ref "IC7") (pin "6") (pinfunction "O_6") (pintype "tri_state"))
      (node (ref "JP2") (pin "12") (pinfunction "12_12") (pintype "passive"))
      (node (ref "L2-V2") (pin "16") (pinfunction "16_16") (pintype "passive"))
    )
    (net (code "260") (name "OP1") (class "Default")
      (node (ref "IC4") (pin "3") (pinfunction "O_3") (pintype "tri_state"))
      (node (ref "JP1") (pin "13") (pinfunction "13_13") (pintype "passive"))
      (node (ref "L1-V1") (pin "15") (pinfunction "15_15") (pintype "passive"))
    )
    (net (code "261") (name "OP2") (class "Default")
      (node (ref "IC7") (pin "8") (pinfunction "O_8") (pintype "tri_state"))
      (node (ref "JP2") (pin "13") (pinfunction "13_13") (pintype "passive"))
      (node (ref "L2-V2") (pin "15") (pinfunction "15_15") (pintype "passive"))
    )
    (net (code "262") (name "OR1") (class "Default")
      (node (ref "IC4") (pin "6") (pinfunction "O_6") (pintype "tri_state"))
      (node (ref "JP1") (pin "14") (pinfunction "14_14") (pintype "passive"))
      (node (ref "L1-V1") (pin "14") (pinfunction "14_14") (pintype "passive"))
    )
    (net (code "263") (name "OR2") (class "Default")
      (node (ref "IC7") (pin "11") (pinfunction "O_11") (pintype "tri_state"))
      (node (ref "JP2") (pin "14") (pinfunction "14_14") (pintype "passive"))
      (node (ref "L2-V2") (pin "14") (pinfunction "14_14") (pintype "passive"))
    )
    (net (code "264") (name "OS1") (class "Default")
      (node (ref "IC4") (pin "8") (pinfunction "O_8") (pintype "tri_state"))
      (node (ref "JP1") (pin "15") (pinfunction "15_15") (pintype "passive"))
      (node (ref "L1-V1") (pin "13") (pinfunction "13_13") (pintype "passive"))
    )
    (net (code "265") (name "OS2") (class "Default")
      (node (ref "IC8") (pin "3") (pinfunction "O_3") (pintype "tri_state"))
      (node (ref "JP2") (pin "15") (pinfunction "15_15") (pintype "passive"))
      (node (ref "L2-V2") (pin "13") (pinfunction "13_13") (pintype "passive"))
    )
    (net (code "266") (name "OT2") (class "Default")
      (node (ref "IC8") (pin "6") (pinfunction "O_6") (pintype "tri_state"))
      (node (ref "JP2") (pin "16") (pinfunction "16_16") (pintype "passive"))
      (node (ref "L2-V2") (pin "12") (pinfunction "12_12") (pintype "passive"))
    )
    (net (code "267") (name "OU1") (class "Default")
      (node (ref "IC4") (pin "11") (pinfunction "O_11") (pintype "tri_state"))
      (node (ref "JP1") (pin "17") (pinfunction "17_17") (pintype "passive"))
      (node (ref "L1-V1") (pin "11") (pinfunction "11_11") (pintype "passive"))
    )
    (net (code "268") (name "OU2") (class "Default")
      (node (ref "IC8") (pin "8") (pinfunction "O_8") (pintype "tri_state"))
      (node (ref "JP2") (pin "17") (pinfunction "17_17") (pintype "passive"))
      (node (ref "L2-V2") (pin "11") (pinfunction "11_11") (pintype "passive"))
    )
    (net (code "269") (name "OV1") (class "Default")
      (node (ref "IC5") (pin "3") (pinfunction "O_3") (pintype "tri_state"))
      (node (ref "JP1") (pin "18") (pinfunction "18_18") (pintype "passive"))
      (node (ref "L1-V1") (pin "10") (pinfunction "10_10") (pintype "passive"))
    )
    (net (code "270") (name "OV2") (class "Default")
      (node (ref "IC8") (pin "11") (pinfunction "O_11") (pintype "tri_state"))
      (node (ref "JP2") (pin "18") (pinfunction "18_18") (pintype "passive"))
      (node (ref "L2-V2") (pin "10") (pinfunction "10_10") (pintype "passive"))
    )
    (net (code "271") (name "P1") (class "Default")
      (node (ref "IN1-2") (pin "10") (pinfunction "10_10") (pintype "passive"))
      (node (ref "JP3") (pin "13") (pinfunction "13_13") (pintype "passive"))
      (node (ref "L1-V1") (pin "4") (pinfunction "4_4") (pintype "passive"))
      (node (ref "SIDE1") (pin "30") (pinfunction "30_30") (pintype "passive"))
    )
    (net (code "272") (name "P2") (class "Default")
      (node (ref "IN3-4") (pin "13") (pinfunction "13_13") (pintype "passive"))
      (node (ref "JP4") (pin "13") (pinfunction "13_13") (pintype "passive"))
      (node (ref "L2-V2") (pin "4") (pinfunction "4_4") (pintype "passive"))
      (node (ref "SIDE2") (pin "24") (pinfunction "24_24") (pintype "passive"))
    )
    (net (code "273") (name "PIA-B5") (class "Default")
      (node (ref "CORE-IO") (pin "18") (pinfunction "18_18") (pintype "passive"))
      (node (ref "IC9") (pin "5") (pinfunction "I1_5") (pintype "input"))
    )
    (net (code "274") (name "PIA-B7") (class "Default")
      (node (ref "CORE-IO") (pin "20") (pinfunction "20_20") (pintype "passive"))
      (node (ref "IC9") (pin "1") (pinfunction "I0_1") (pintype "input"))
      (node (ref "IC9") (pin "2") (pinfunction "I1_2") (pintype "input"))
    )
    (net (code "275") (name "R1") (class "Default")
      (node (ref "IN1-2") (pin "12") (pinfunction "12_12") (pintype "passive"))
      (node (ref "JP3") (pin "14") (pinfunction "14_14") (pintype "passive"))
      (node (ref "L1-V1") (pin "5") (pinfunction "5_5") (pintype "passive"))
      (node (ref "SIDE1") (pin "26") (pinfunction "26_26") (pintype "passive"))
    )
    (net (code "276") (name "R2") (class "Default")
      (node (ref "IN3-4") (pin "15") (pinfunction "15_15") (pintype "passive"))
      (node (ref "JP4") (pin "14") (pinfunction "14_14") (pintype "passive"))
      (node (ref "L2-V2") (pin "5") (pinfunction "5_5") (pintype "passive"))
      (node (ref "SIDE2") (pin "26") (pinfunction "26_26") (pintype "passive"))
    )
    (net (code "277") (name "S1") (class "Default")
      (node (ref "IN1-2") (pin "14") (pinfunction "14_14") (pintype "passive"))
      (node (ref "JP3") (pin "15") (pinfunction "15_15") (pintype "passive"))
      (node (ref "L1-V1") (pin "6") (pinfunction "6_6") (pintype "passive"))
      (node (ref "SIDE1") (pin "32") (pinfunction "32_32") (pintype "passive"))
    )
    (net (code "278") (name "S2") (class "Default")
      (node (ref "IN3-4") (pin "10") (pinfunction "10_10") (pintype "passive"))
      (node (ref "JP4") (pin "15") (pinfunction "15_15") (pintype "passive"))
      (node (ref "L2-V2") (pin "6") (pinfunction "6_6") (pintype "passive"))
      (node (ref "SIDE2") (pin "28") (pinfunction "28_28") (pintype "passive"))
    )
    (net (code "279") (name "T1") (class "Default")
      (node (ref "JP3") (pin "16") (pinfunction "16_16") (pintype "passive"))
      (node (ref "L1-V1") (pin "7") (pinfunction "7_7") (pintype "passive"))
      (node (ref "SIDE1") (pin "34") (pinfunction "34_34") (pintype "passive"))
    )
    (net (code "280") (name "T2") (class "Default")
      (node (ref "IN3-4") (pin "12") (pinfunction "12_12") (pintype "passive"))
      (node (ref "JP4") (pin "16") (pinfunction "16_16") (pintype "passive"))
      (node (ref "L2-V2") (pin "7") (pinfunction "7_7") (pintype "passive"))
      (node (ref "SIDE2") (pin "30") (pinfunction "30_30") (pintype "passive"))
    )
    (net (code "281") (name "U1") (class "Default")
      (node (ref "IN1-2") (pin "16") (pinfunction "16_16") (pintype "passive"))
      (node (ref "JP3") (pin "17") (pinfunction "17_17") (pintype "passive"))
      (node (ref "L1-V1") (pin "8") (pinfunction "8_8") (pintype "passive"))
      (node (ref "SIDE1") (pin "4") (pinfunction "4_4") (pintype "passive"))
    )
    (net (code "282") (name "U2") (class "Default")
      (node (ref "IN3-4") (pin "14") (pinfunction "14_14") (pintype "passive"))
      (node (ref "JP4") (pin "17") (pinfunction "17_17") (pintype "passive"))
      (node (ref "L2-V2") (pin "8") (pinfunction "8_8") (pintype "passive"))
      (node (ref "SIDE2") (pin "34") (pinfunction "34_34") (pintype "passive"))
    )
    (net (code "283") (name "V1") (class "Default")
      (node (ref "IN3-4") (pin "1") (pinfunction "1_1") (pintype "passive"))
      (node (ref "JP3") (pin "18") (pinfunction "18_18") (pintype "passive"))
      (node (ref "L1-V1") (pin "9") (pinfunction "9_9") (pintype "passive"))
      (node (ref "SIDE1") (pin "2") (pinfunction "2_2") (pintype "passive"))
    )
    (net (code "284") (name "V2") (class "Default")
      (node (ref "IN3-4") (pin "16") (pinfunction "16_16") (pintype "passive"))
      (node (ref "JP4") (pin "18") (pinfunction "18_18") (pintype "passive"))
      (node (ref "L2-V2") (pin "9") (pinfunction "9_9") (pintype "passive"))
      (node (ref "SIDE2") (pin "32") (pinfunction "32_32") (pintype "passive"))
    )
    (net (code "285") (name "VCC") (class "Default")
      (node (ref "A2-K2") (pin "18") (pinfunction "18_18") (pintype "passive"))
      (node (ref "BYP1") (pin "1") (pinfunction "1_1") (pintype "passive"))
      (node (ref "BYP10") (pin "1") (pinfunction "1_1") (pintype "passive"))
      (node (ref "BYP2") (pin "1") (pinfunction "1_1") (pintype "passive"))
      (node (ref "BYP3") (pin "1") (pinfunction "1_1") (pintype "passive"))
      (node (ref "BYP4") (pin "1") (pinfunction "1_1") (pintype "passive"))
      (node (ref "BYP5") (pin "1") (pinfunction "1_1") (pintype "passive"))
      (node (ref "BYP6") (pin "1") (pinfunction "1_1") (pintype "passive"))
      (node (ref "BYP7") (pin "1") (pinfunction "1_1") (pintype "passive"))
      (node (ref "BYP8") (pin "1") (pinfunction "1_1") (pintype "passive"))
      (node (ref "BYP9") (pin "1") (pinfunction "1_1") (pintype "passive"))
      (node (ref "CORE-IO") (pin "12") (pinfunction "12_12") (pintype "passive"))
      (node (ref "CORE-IO") (pin "9") (pinfunction "9_9") (pintype "passive"))
      (node (ref "JP2") (pin "1") (pinfunction "1_1") (pintype "passive"))
      (node (ref "POWER") (pin "2") (pinfunction "2_2") (pintype "passive"))
      (node (ref "RN1") (pin "1") (pinfunction "1_1") (pintype "passive"))
      (node (ref "RN2") (pin "1") (pinfunction "1_1") (pintype "passive"))
      (node (ref "RN3") (pin "1") (pinfunction "1_1") (pintype "passive"))
      (node (ref "RN4") (pin "1") (pinfunction "1_1") (pintype "passive"))
    )
    (net (code "286") (name "unconnected-(CORE-IO-Pad1)") (class "Default")
      (node (ref "CORE-IO") (pin "1") (pinfunction "1_1") (pintype "passive"))
    )
    (net (code "287") (name "unconnected-(CORE-IO-Pad2)") (class "Default")
      (node (ref "CORE-IO") (pin "2") (pinfunction "2_2") (pintype "passive"))
    )
    (net (code "288") (name "unconnected-(CORE-IO-Pad3)") (class "Default")
      (node (ref "CORE-IO") (pin "3") (pinfunction "3_3") (pintype "passive"))
    )
    (net (code "289") (name "unconnected-(CORE-IO-Pad4)") (class "Default")
      (node (ref "CORE-IO") (pin "4") (pinfunction "4_4") (pintype "passive"))
    )
    (net (code "290") (name "unconnected-(CORE-IO-Pad5)") (class "Default")
      (node (ref "CORE-IO") (pin "5") (pinfunction "5_5") (pintype "passive"))
    )
    (net (code "291") (name "unconnected-(CORE-IO-Pad6)") (class "Default")
      (node (ref "CORE-IO") (pin "6") (pinfunction "6_6") (pintype "passive"))
    )
    (net (code "292") (name "unconnected-(CORE-IO-Pad7)") (class "Default")
      (node (ref "CORE-IO") (pin "7") (pinfunction "7_7") (pintype "passive"))
    )
    (net (code "293") (name "unconnected-(CORE-IO-Pad8)") (class "Default")
      (node (ref "CORE-IO") (pin "8") (pinfunction "8_8") (pintype "passive"))
    )
    (net (code "294") (name "unconnected-(CORE-IO-Pad13)") (class "Default")
      (node (ref "CORE-IO") (pin "13") (pinfunction "13_13") (pintype "passive"))
    )
    (net (code "295") (name "unconnected-(CORE-IO-Pad14)") (class "Default")
      (node (ref "CORE-IO") (pin "14") (pinfunction "14_14") (pintype "passive"))
    )
    (net (code "296") (name "unconnected-(CORE-IO-Pad15)") (class "Default")
      (node (ref "CORE-IO") (pin "15") (pinfunction "15_15") (pintype "passive"))
    )
    (net (code "297") (name "unconnected-(CORE-IO-Pad16)") (class "Default")
      (node (ref "CORE-IO") (pin "16") (pinfunction "16_16") (pintype "passive"))
    )
    (net (code "298") (name "unconnected-(CORE-IO-Pad17)") (class "Default")
      (node (ref "CORE-IO") (pin "17") (pinfunction "17_17") (pintype "passive"))
    )
    (net (code "299") (name "unconnected-(CORE-IO-Pad19)") (class "Default")
      (node (ref "CORE-IO") (pin "19") (pinfunction "19_19") (pintype "passive"))
    )
    (net (code "300") (name "unconnected-(IN5-6-Pad2)") (class "Default")
      (node (ref "IN5-6") (pin "2") (pinfunction "2_2") (pintype "passive"))
    )
    (net (code "301") (name "unconnected-(IN5-6-Pad3)") (class "Default")
      (node (ref "IN5-6") (pin "3") (pinfunction "3_3") (pintype "passive"))
    )
    (net (code "302") (name "unconnected-(IN5-6-Pad4)") (class "Default")
      (node (ref "IN5-6") (pin "4") (pinfunction "4_4") (pintype "passive"))
    )
    (net (code "303") (name "unconnected-(IN5-6-Pad5)") (class "Default")
      (node (ref "IN5-6") (pin "5") (pinfunction "5_5") (pintype "passive"))
    )
    (net (code "304") (name "unconnected-(IN5-6-Pad6)") (class "Default")
      (node (ref "IN5-6") (pin "6") (pinfunction "6_6") (pintype "passive"))
    )
    (net (code "305") (name "unconnected-(IN5-6-Pad7)") (class "Default")
      (node (ref "IN5-6") (pin "7") (pinfunction "7_7") (pintype "passive"))
    )
    (net (code "306") (name "unconnected-(IN5-6-Pad8)") (class "Default")
      (node (ref "IN5-6") (pin "8") (pinfunction "8_8") (pintype "passive"))
    )
    (net (code "307") (name "unconnected-(IN5-6-Pad9)") (class "Default")
      (node (ref "IN5-6") (pin "9") (pinfunction "9_9") (pintype "passive"))
    )
    (net (code "308") (name "unconnected-(IN5-6-Pad10)") (class "Default")
      (node (ref "IN5-6") (pin "10") (pinfunction "10_10") (pintype "passive"))
    )
    (net (code "309") (name "unconnected-(IN5-6-Pad11)") (class "Default")
      (node (ref "IN5-6") (pin "11") (pinfunction "11_11") (pintype "passive"))
    )
    (net (code "310") (name "unconnected-(IN5-6-Pad12)") (class "Default")
      (node (ref "IN5-6") (pin "12") (pinfunction "12_12") (pintype "passive"))
    )
    (net (code "311") (name "unconnected-(IN5-6-Pad13)") (class "Default")
      (node (ref "IN5-6") (pin "13") (pinfunction "13_13") (pintype "passive"))
    )
    (net (code "312") (name "unconnected-(IN5-6-Pad14)") (class "Default")
      (node (ref "IN5-6") (pin "14") (pinfunction "14_14") (pintype "passive"))
    )
    (net (code "313") (name "unconnected-(IN5-6-Pad15)") (class "Default")
      (node (ref "IN5-6") (pin "15") (pinfunction "15_15") (pintype "passive"))
    )
    (net (code "314") (name "unconnected-(IN5-6-Pad16)") (class "Default")
      (node (ref "IN5-6") (pin "16") (pinfunction "16_16") (pintype "passive"))
    )
    (net (code "315") (name "unconnected-(RN1-Pad10)") (class "Default")
      (node (ref "RN1") (pin "10") (pinfunction "10_10") (pintype "passive"))
    )
    (net (code "316") (name "unconnected-(RN1-Pad11)") (class "Default")
      (node (ref "RN1") (pin "11") (pinfunction "11_11") (pintype "passive"))
    )
    (net (code "317") (name "unconnected-(RN2-Pad10)") (class "Default")
      (node (ref "RN2") (pin "10") (pinfunction "10_10") (pintype "passive"))
    )
    (net (code "318") (name "unconnected-(RN2-Pad11)") (class "Default")
      (node (ref "RN2") (pin "11") (pinfunction "11_11") (pintype "passive"))
    )
    (net (code "319") (name "unconnected-(RN3-Pad10)") (class "Default")
      (node (ref "RN3") (pin "10") (pinfunction "10_10") (pintype "passive"))
    )
    (net (code "320") (name "unconnected-(RN3-Pad11)") (class "Default")
      (node (ref "RN3") (pin "11") (pinfunction "11_11") (pintype "passive"))
    )
    (net (code "321") (name "unconnected-(RN4-Pad10)") (class "Default")
      (node (ref "RN4") (pin "10") (pinfunction "10_10") (pintype "passive"))
    )
    (net (code "322") (name "unconnected-(RN4-Pad11)") (class "Default")
      (node (ref "RN4") (pin "11") (pinfunction "11_11") (pintype "passive"))
    )
    (net (code "323") (name "~{MR}") (class "Default")
      (node (ref "!MR") (pin "1") (pinfunction "1_1") (pintype "passive"))
      (node (ref "IC9") (pin "11") (pinfunction "O_11") (pintype "output"))
      (node (ref "IC9") (pin "9") (pinfunction "I0_9") (pintype "input"))
    )
  )
)
